# RTK_Mosaic_X5.net
KiCad netlist of a schematic drawn in EAGLE
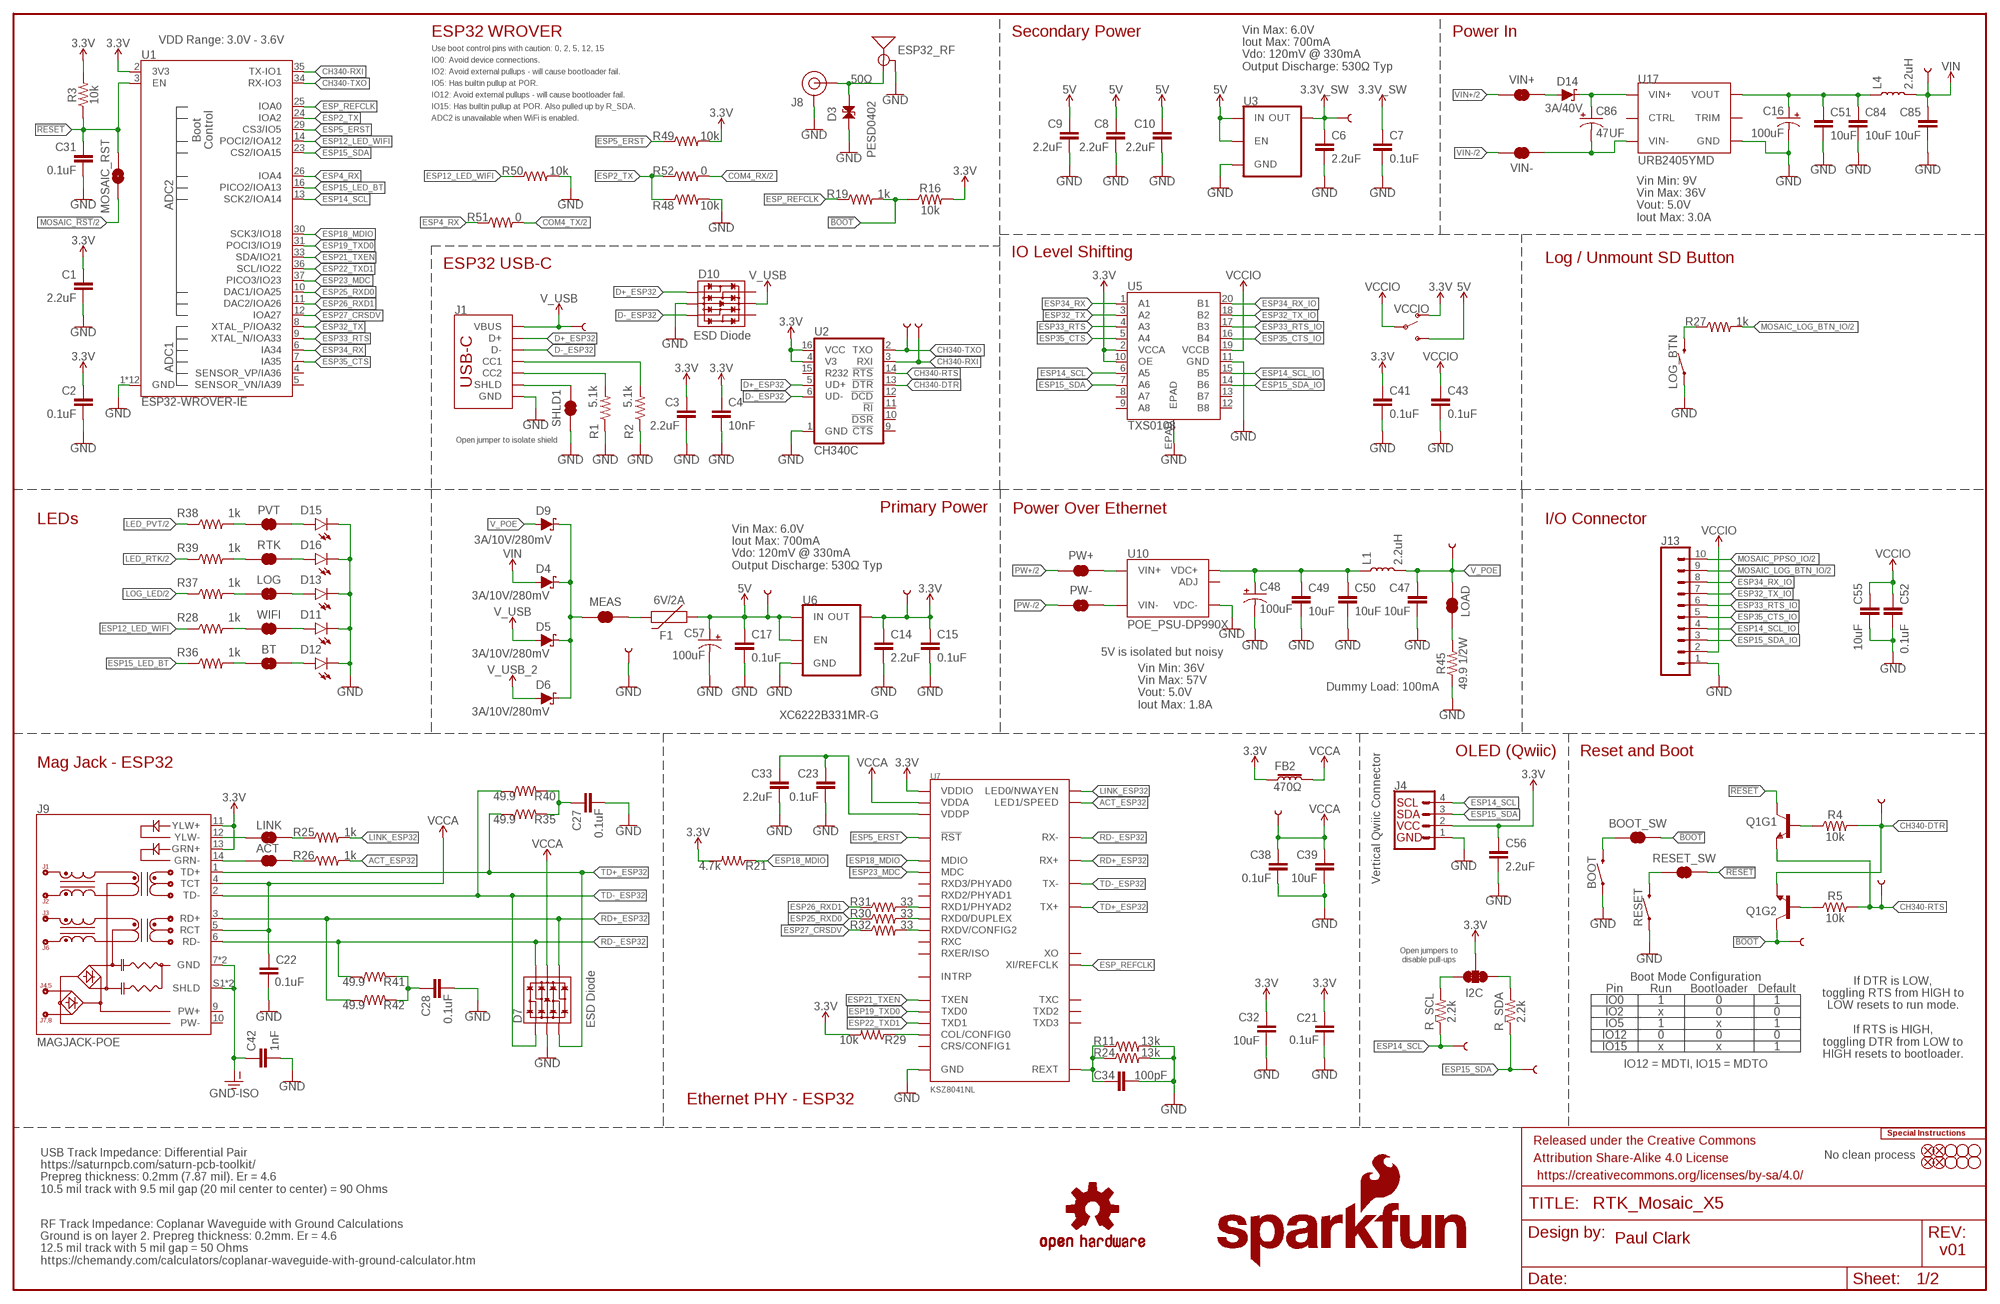
[diagram p0: schematic, sheet 1]
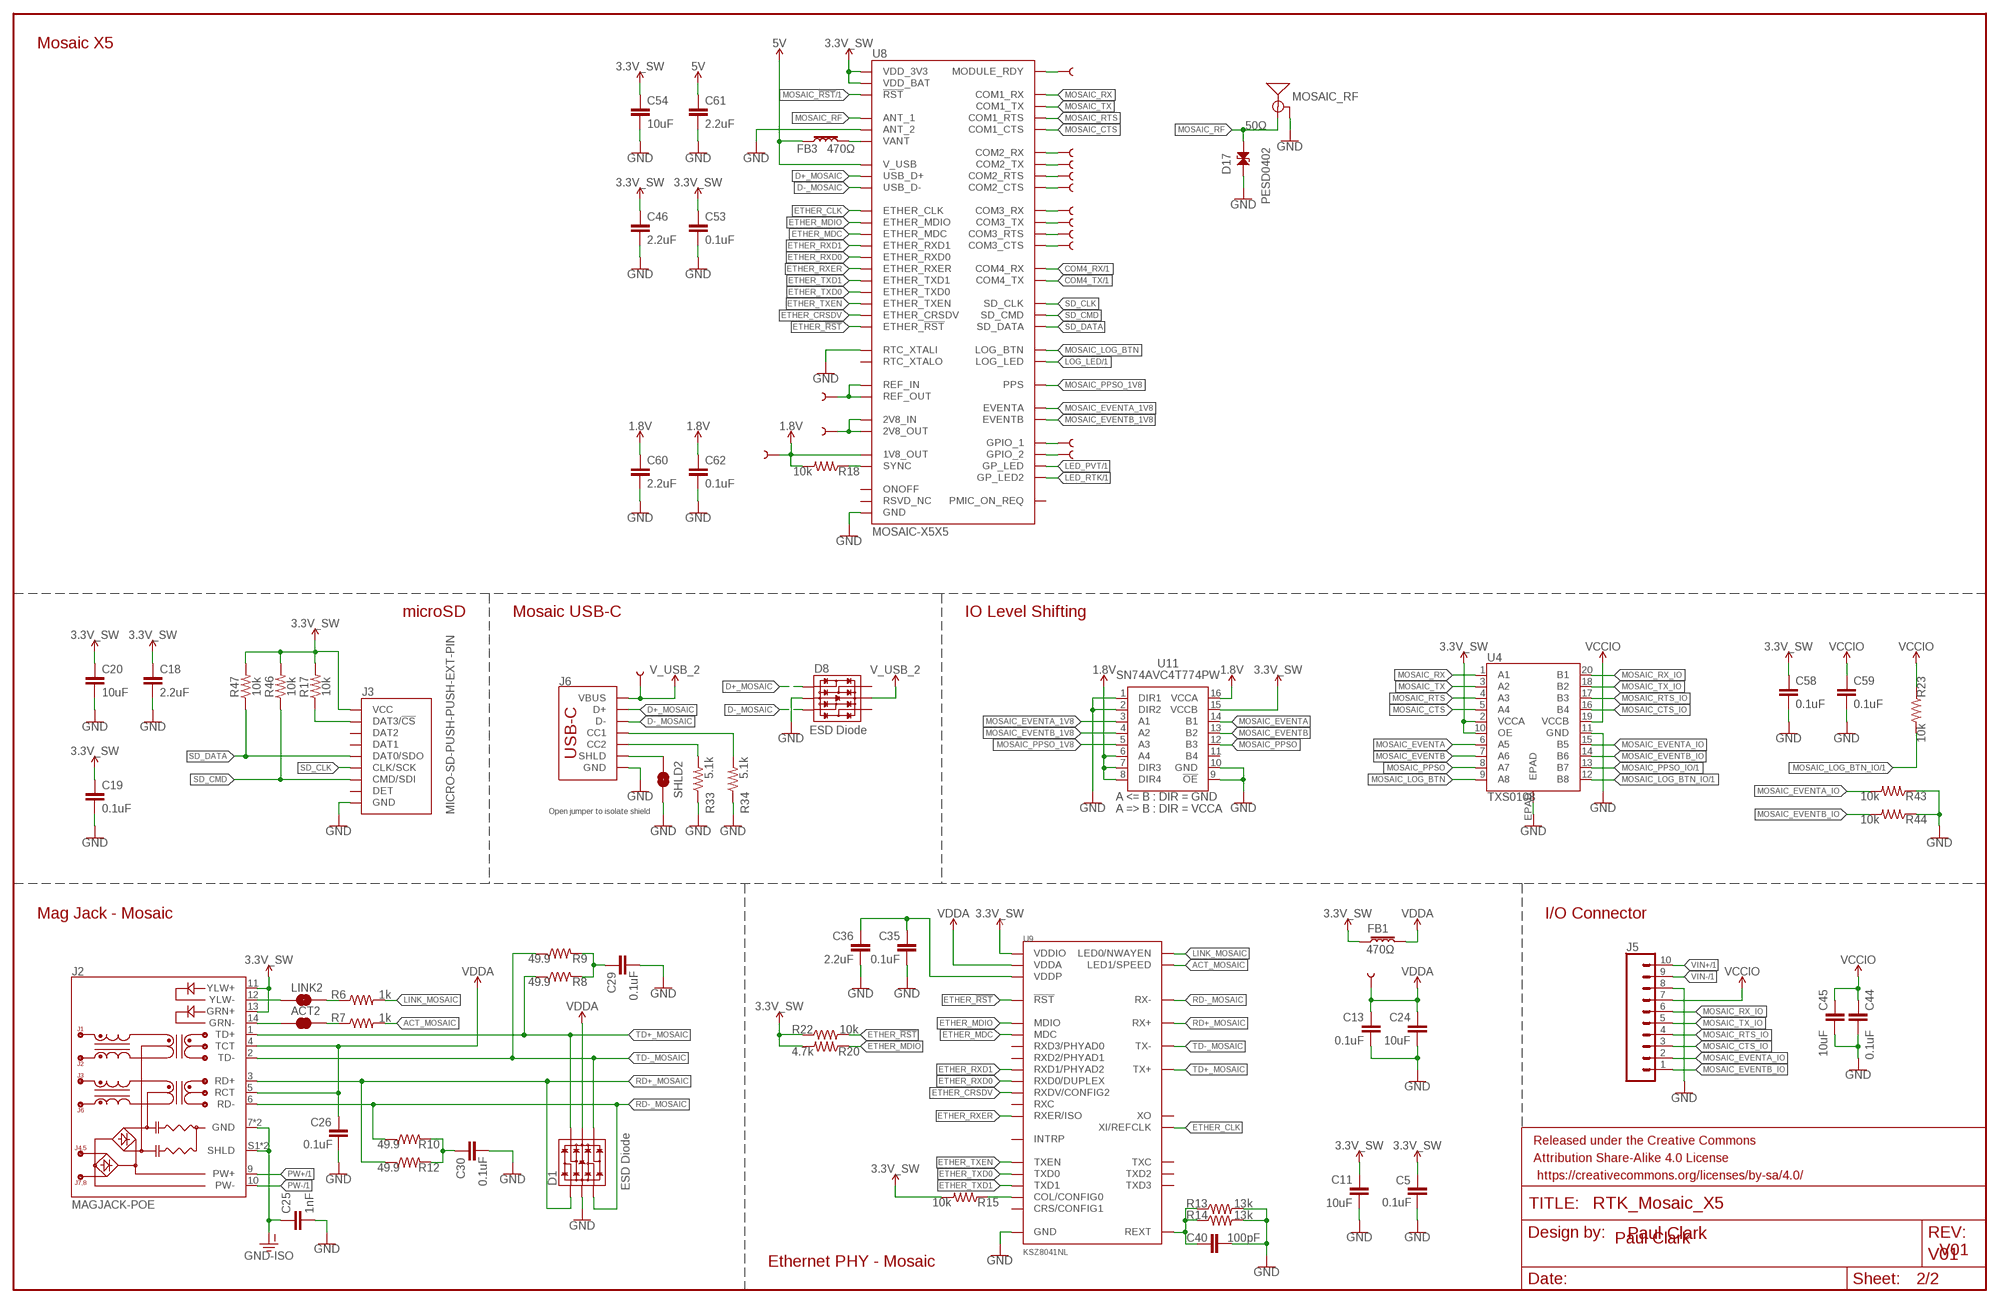
[diagram p1: schematic, sheet 2]

(export (version "E")
  (design (tool "Eeschema 10.0.6"))
  (components
    (comp (ref "3V3")
      (value "TEST-POINTPOGO_PTH")
      (footprint "eagle-import:1X01_NO_SILK")
      (libsource (lib "eagle-import") (part "TEST-POINTPOGO_PTH"))
    )
    (comp (ref "3V3_SW")
      (value "TEST-POINTPOGO_PTH")
      (footprint "eagle-import:1X01_NO_SILK")
      (libsource (lib "eagle-import") (part "TEST-POINTPOGO_PTH"))
    )
    (comp (ref "5V")
      (value "TEST-POINTPOGO_PTH")
      (footprint "eagle-import:1X01_NO_SILK")
      (libsource (lib "eagle-import") (part "TEST-POINTPOGO_PTH"))
    )
    (comp (ref "ACT")
      (value "JUMPER-SMT_2_NC_TRACE_SILK")
      (footprint "eagle-import:SMT-JUMPER_2_NC_TRACE_SILK")
      (libsource (lib "eagle-import") (part "JUMPER-SMT_2_NC_TRACE_SILK"))
    )
    (comp (ref "BOOT")
      (value "MOMENTARY-SWITCH-SPST-PTH-RIGHT-ANGLE-8-020")
      (footprint "eagle-import:TACTILE_SWITCH_PTH_RA_8-020")
      (libsource (lib "eagle-import") (part "MOMENTARY-SWITCH-SPST-PTH-RIGHT-ANGLE-8-020"))
    )
    (comp (ref "BOOT_SW")
      (value "JUMPER-SMT_2_NC_TRACE_SILK")
      (footprint "eagle-import:SMT-JUMPER_2_NC_TRACE_SILK")
      (libsource (lib "eagle-import") (part "JUMPER-SMT_2_NC_TRACE_SILK"))
    )
    (comp (ref "BT")
      (value "JUMPER-SMT_2_NC_TRACE_SILK")
      (footprint "eagle-import:SMT-JUMPER_2_NC_TRACE_SILK")
      (libsource (lib "eagle-import") (part "JUMPER-SMT_2_NC_TRACE_SILK"))
    )
    (comp (ref "C1")
      (value "2.2uF")
      (footprint "eagle-import:0603")
      (libsource (lib "eagle-import") (part "2.2UF-0603-10V-20%"))
    )
    (comp (ref "C2")
      (value "0.1uF")
      (footprint "eagle-import:0603")
      (libsource (lib "eagle-import") (part "0.1UF-0603-25V-5%"))
    )
    (comp (ref "C3")
      (value "2.2uF")
      (footprint "eagle-import:0603")
      (libsource (lib "eagle-import") (part "2.2UF-0603-10V-20%"))
    )
    (comp (ref "C4")
      (value "10nF")
      (footprint "eagle-import:0603")
      (libsource (lib "eagle-import") (part "10NF-0603-50V-10%"))
    )
    (comp (ref "C6")
      (value "2.2uF")
      (footprint "eagle-import:0603")
      (libsource (lib "eagle-import") (part "2.2UF-0603-10V-20%"))
    )
    (comp (ref "C7")
      (value "0.1uF")
      (footprint "eagle-import:0603")
      (libsource (lib "eagle-import") (part "0.1UF-0603-25V-5%"))
    )
    (comp (ref "C8")
      (value "2.2uF")
      (footprint "eagle-import:0603")
      (libsource (lib "eagle-import") (part "2.2UF-0603-10V-20%"))
    )
    (comp (ref "C9")
      (value "2.2uF")
      (footprint "eagle-import:0603")
      (libsource (lib "eagle-import") (part "2.2UF-0603-10V-20%"))
    )
    (comp (ref "C10")
      (value "2.2uF")
      (footprint "eagle-import:0603")
      (libsource (lib "eagle-import") (part "2.2UF-0603-10V-20%"))
    )
    (comp (ref "C14")
      (value "2.2uF")
      (footprint "eagle-import:0603")
      (libsource (lib "eagle-import") (part "2.2UF-0603-10V-20%"))
    )
    (comp (ref "C15")
      (value "0.1uF")
      (footprint "eagle-import:0603")
      (libsource (lib "eagle-import") (part "0.1UF-0603-25V-5%"))
    )
    (comp (ref "C16")
      (value "100uF")
      (footprint "eagle-import:PANASONIC_D")
      (libsource (lib "eagle-import") (part "100UF-POLAR-25V-20%(ELEC)"))
    )
    (comp (ref "C17")
      (value "0.1uF")
      (footprint "eagle-import:0603")
      (libsource (lib "eagle-import") (part "0.1UF-0603-25V-5%"))
    )
    (comp (ref "C21")
      (value "0.1uF")
      (footprint "eagle-import:0603")
      (libsource (lib "eagle-import") (part "0.1UF-0603-25V-5%"))
    )
    (comp (ref "C22")
      (value "0.1uF")
      (footprint "eagle-import:0603")
      (libsource (lib "eagle-import") (part "0.1UF-0603-25V-5%"))
    )
    (comp (ref "C23")
      (value "0.1uF")
      (footprint "eagle-import:0603")
      (libsource (lib "eagle-import") (part "0.1UF-0603-25V-5%"))
    )
    (comp (ref "C27")
      (value "0.1uF")
      (footprint "eagle-import:0603")
      (libsource (lib "eagle-import") (part "0.1UF-0603-25V-5%"))
    )
    (comp (ref "C28")
      (value "0.1uF")
      (footprint "eagle-import:0603")
      (libsource (lib "eagle-import") (part "0.1UF-0603-25V-5%"))
    )
    (comp (ref "C31")
      (value "0.1uF")
      (footprint "eagle-import:0603")
      (libsource (lib "eagle-import") (part "0.1UF-0603-25V-5%"))
    )
    (comp (ref "C32")
      (value "10uF")
      (footprint "eagle-import:0603")
      (libsource (lib "eagle-import") (part "10UF-0603-6.3V-20%"))
    )
    (comp (ref "C33")
      (value "2.2uF")
      (footprint "eagle-import:0603")
      (libsource (lib "eagle-import") (part "2.2UF-0603-10V-20%"))
    )
    (comp (ref "C34")
      (value "100pF")
      (footprint "eagle-import:0603")
      (libsource (lib "eagle-import") (part "100PF-0603-50V-5%"))
    )
    (comp (ref "C38")
      (value "0.1uF")
      (footprint "eagle-import:0603")
      (libsource (lib "eagle-import") (part "0.1UF-0603-25V-5%"))
    )
    (comp (ref "C39")
      (value "10uF")
      (footprint "eagle-import:0603")
      (libsource (lib "eagle-import") (part "10UF-0603-6.3V-20%"))
    )
    (comp (ref "C41")
      (value "0.1uF")
      (footprint "eagle-import:0603")
      (libsource (lib "eagle-import") (part "0.1UF-0603-25V-5%"))
    )
    (comp (ref "C42")
      (value "1nF")
      (footprint "eagle-import:1206")
      (libsource (lib "eagle-import") (part "1.0NF/1000PF-1206-2KV-10%"))
    )
    (comp (ref "C43")
      (value "0.1uF")
      (footprint "eagle-import:0603")
      (libsource (lib "eagle-import") (part "0.1UF-0603-25V-5%"))
    )
    (comp (ref "C47")
      (value "10uF")
      (footprint "eagle-import:0805")
      (libsource (lib "eagle-import") (part "10UF-0805-25V-10%"))
    )
    (comp (ref "C48")
      (value "100uF")
      (footprint "eagle-import:PANASONIC_D")
      (libsource (lib "eagle-import") (part "100UF-POLAR-25V-20%(ELEC)"))
    )
    (comp (ref "C49")
      (value "10uF")
      (footprint "eagle-import:0805")
      (libsource (lib "eagle-import") (part "10UF-0805-25V-10%"))
    )
    (comp (ref "C50")
      (value "10uF")
      (footprint "eagle-import:0805")
      (libsource (lib "eagle-import") (part "10UF-0805-25V-10%"))
    )
    (comp (ref "C51")
      (value "10uF")
      (footprint "eagle-import:0805")
      (libsource (lib "eagle-import") (part "10UF-0805-25V-10%"))
    )
    (comp (ref "C52")
      (value "0.1uF")
      (footprint "eagle-import:0603")
      (libsource (lib "eagle-import") (part "0.1UF-0603-25V-5%"))
    )
    (comp (ref "C55")
      (value "10uF")
      (footprint "eagle-import:0603")
      (libsource (lib "eagle-import") (part "10UF-0603-6.3V-20%"))
    )
    (comp (ref "C56")
      (value "2.2uF")
      (footprint "eagle-import:0603")
      (libsource (lib "eagle-import") (part "2.2UF-0603-10V-20%"))
    )
    (comp (ref "C57")
      (value "100uF")
      (footprint "eagle-import:PANASONIC_D")
      (libsource (lib "eagle-import") (part "100UF-POLAR-25V-20%(ELEC)"))
    )
    (comp (ref "C84")
      (value "10uF")
      (footprint "eagle-import:0805")
      (libsource (lib "eagle-import") (part "10UF-0805-25V-10%"))
    )
    (comp (ref "C85")
      (value "10uF")
      (footprint "eagle-import:0805")
      (libsource (lib "eagle-import") (part "10UF-0805-25V-10%"))
    )
    (comp (ref "C86")
      (value "47UF")
      (footprint "eagle-import:PANASONIC_D")
      (libsource (lib "eagle-import") (part "47UF-POLAR-PANASONIC_D-50V-20%"))
    )
    (comp (ref "D3")
      (value "PESD0402")
      (footprint "eagle-import:0402")
      (fields
        (field (name "DIGIKEY_PART") "PESD0402-140CT-ND")
        (field (name "MOUSE_PART") "650-PESD0402-140")
      )
      (libsource (lib "eagle-import") (part "PESD0402-0402"))
    )
    (comp (ref "D4")
      (value "3A/10V/280mV")
      (footprint "eagle-import:SOD-323")
      (libsource (lib "eagle-import") (part "DIODE-SCHOTTKY-BAT60A"))
    )
    (comp (ref "D5")
      (value "3A/10V/280mV")
      (footprint "eagle-import:SOD-323")
      (libsource (lib "eagle-import") (part "DIODE-SCHOTTKY-BAT60A"))
    )
    (comp (ref "D6")
      (value "3A/10V/280mV")
      (footprint "eagle-import:SOD-323")
      (libsource (lib "eagle-import") (part "DIODE-SCHOTTKY-BAT60A"))
    )
    (comp (ref "D7")
      (value "ESD Diode")
      (footprint "eagle-import:SOT-23-6")
      (libsource (lib "eagle-import") (part "TVS_DIODE_ARRAY_DT1042-04SO-7"))
    )
    (comp (ref "D9")
      (value "3A/10V/280mV")
      (footprint "eagle-import:SOD-323")
      (libsource (lib "eagle-import") (part "DIODE-SCHOTTKY-BAT60A"))
    )
    (comp (ref "D10")
      (value "ESD Diode")
      (footprint "eagle-import:SOT-23-6")
      (libsource (lib "eagle-import") (part "TVS_DIODE_ARRAY_DT1042-04SO-7"))
    )
    (comp (ref "D11")
      (value "LED-RIGHT-ANGLE-PTH-AMBER")
      (footprint "eagle-import:CBI-RIGHT-ANGLE-PTH")
      (libsource (lib "eagle-import") (part "LED-RIGHT-ANGLE-PTH-AMBER"))
    )
    (comp (ref "D12")
      (value "LED-RIGHT-ANGLE-PTH-BLUE")
      (footprint "eagle-import:CBI-RIGHT-ANGLE-PTH")
      (libsource (lib "eagle-import") (part "LED-RIGHT-ANGLE-PTH-BLUE"))
    )
    (comp (ref "D13")
      (value "LED-RIGHT-ANGLE-PTH-GREEN")
      (footprint "eagle-import:CBI-RIGHT-ANGLE-PTH")
      (libsource (lib "eagle-import") (part "LED-RIGHT-ANGLE-PTH-GREEN"))
    )
    (comp (ref "D14")
      (value "3A/40V")
      (footprint "eagle-import:SMA-DIODE")
      (libsource (lib "eagle-import") (part "DIODE-SCHOTTKY-B340A"))
    )
    (comp (ref "D15")
      (value "LED-RIGHT-ANGLE-PTH-BLUE")
      (footprint "eagle-import:CBI-RIGHT-ANGLE-PTH")
      (libsource (lib "eagle-import") (part "LED-RIGHT-ANGLE-PTH-BLUE"))
    )
    (comp (ref "D16")
      (value "LED-RIGHT-ANGLE-PTH-BLUE")
      (footprint "eagle-import:CBI-RIGHT-ANGLE-PTH")
      (libsource (lib "eagle-import") (part "LED-RIGHT-ANGLE-PTH-BLUE"))
    )
    (comp (ref "DTR")
      (value "TEST-POINTPOGO_PTH")
      (footprint "eagle-import:1X01_NO_SILK")
      (libsource (lib "eagle-import") (part "TEST-POINTPOGO_PTH"))
    )
    (comp (ref "ESP32_RF")
      (value "ANTENNA-SMA-GROUNDEDEDGE_RPSMA")
      (footprint "eagle-import:RP-SMA-EDGE")
      (libsource (lib "eagle-import") (part "ANTENNA-SMA-GROUNDEDEDGE_RPSMA"))
    )
    (comp (ref "F1")
      (value "6V/2A")
      (footprint "eagle-import:1210")
      (libsource (lib "eagle-import") (part "PPTC_6V2A"))
    )
    (comp (ref "FB2")
      (value "470Ω")
      (footprint "eagle-import:0603")
      (libsource (lib "eagle-import") (part "FERRITE_BEAD-0603-470Ω-100MHZ-1A-200MILIΩ"))
    )
    (comp (ref "FD1")
      (value "FIDUCIAL1X2")
      (footprint "eagle-import:FIDUCIAL-1X2")
      (libsource (lib "eagle-import") (part "FIDUCIAL1X2"))
    )
    (comp (ref "FD2")
      (value "FIDUCIAL1X2")
      (footprint "eagle-import:FIDUCIAL-1X2")
      (libsource (lib "eagle-import") (part "FIDUCIAL1X2"))
    )
    (comp (ref "FD3")
      (value "FIDUCIAL1X2")
      (footprint "eagle-import:FIDUCIAL-1X2")
      (libsource (lib "eagle-import") (part "FIDUCIAL1X2"))
    )
    (comp (ref "FD4")
      (value "FIDUCIAL1X2")
      (footprint "eagle-import:FIDUCIAL-1X2")
      (libsource (lib "eagle-import") (part "FIDUCIAL1X2"))
    )
    (comp (ref "FRAME1")
      (value "FRAME-LEDGER")
      (footprint "eagle-import:CREATIVE_COMMONS")
      (libsource (lib "eagle-import") (part "FRAME-LEDGER"))
    )
    (comp (ref "GND")
      (value "TEST-POINTPOGO_PTH")
      (footprint "eagle-import:1X01_NO_SILK")
      (libsource (lib "eagle-import") (part "TEST-POINTPOGO_PTH"))
    )
    (comp (ref "H1")
      (value "STAND-OFFTIGHT")
      (footprint "eagle-import:STAND-OFF-TIGHT")
      (libsource (lib "eagle-import") (part "STAND-OFFTIGHT"))
    )
    (comp (ref "H2")
      (value "STAND-OFFTIGHT")
      (footprint "eagle-import:STAND-OFF-TIGHT")
      (libsource (lib "eagle-import") (part "STAND-OFFTIGHT"))
    )
    (comp (ref "H3")
      (value "STAND-OFFTIGHT")
      (footprint "eagle-import:STAND-OFF-TIGHT")
      (libsource (lib "eagle-import") (part "STAND-OFFTIGHT"))
    )
    (comp (ref "H4")
      (value "STAND-OFFTIGHT")
      (footprint "eagle-import:STAND-OFF-TIGHT")
      (libsource (lib "eagle-import") (part "STAND-OFFTIGHT"))
    )
    (comp (ref "H5")
      (value "STAND-OFFTIGHT")
      (footprint "eagle-import:STAND-OFF-TIGHT")
      (libsource (lib "eagle-import") (part "STAND-OFFTIGHT"))
    )
    (comp (ref "H6")
      (value "STAND-OFFTIGHT")
      (footprint "eagle-import:STAND-OFF-TIGHT")
      (libsource (lib "eagle-import") (part "STAND-OFFTIGHT"))
    )
    (comp (ref "I2C")
      (value "JUMPER-SMT_3_2-NC_TRACE_SILK")
      (footprint "eagle-import:SMT-JUMPER_3_2-NC_TRACE_SILK")
      (libsource (lib "eagle-import") (part "JUMPER-SMT_3_2-NC_TRACE_SILK"))
    )
    (comp (ref "J1")
      (value "USB_C_4-LAYER_PADS")
      (footprint "eagle-import:USB-C-16P_4LAYER-PADS")
      (libsource (lib "eagle-import") (part "USB_C_4-LAYER_PADS"))
    )
    (comp (ref "J4")
      (value "Vertical Qwiic Connector")
      (footprint "eagle-import:JST04_1MM_VERT")
      (libsource (lib "eagle-import") (part "QWIIC_CONNECTOR"))
    )
    (comp (ref "J8")
      (value "U.FL2PIN-REDUCED-FOOTPRINT")
      (footprint "eagle-import:U.FL_REDUCED_FOOTPRINT")
      (libsource (lib "eagle-import") (part "U.FL2PIN-REDUCED-FOOTPRINT"))
    )
    (comp (ref "J9")
      (value "MAGJACK-POE")
      (footprint "eagle-import:MAGJACK-SYM_LED")
      (libsource (lib "eagle-import") (part "MAGJACK-POE"))
    )
    (comp (ref "J13")
      (value "CONN_10_3.5MM_RA_HEADER")
      (footprint "eagle-import:1X10_SCREW_TERMINAL_3.5MM")
      (libsource (lib "eagle-import") (part "CONN_10_3.5MM_RA_HEADER"))
    )
    (comp (ref "L1")
      (value "2.2uH")
      (footprint "eagle-import:0805-WIDE")
      (libsource (lib "eagle-import") (part "INDUCTOR-0805_WIDE-2.2UH"))
    )
    (comp (ref "L4")
      (value "2.2uH")
      (footprint "eagle-import:0805-WIDE")
      (libsource (lib "eagle-import") (part "INDUCTOR-0805_WIDE-2.2UH"))
    )
    (comp (ref "LINK")
      (value "JUMPER-SMT_2_NC_TRACE_SILK")
      (footprint "eagle-import:SMT-JUMPER_2_NC_TRACE_SILK")
      (libsource (lib "eagle-import") (part "JUMPER-SMT_2_NC_TRACE_SILK"))
    )
    (comp (ref "LOAD")
      (value "JUMPER-SMT_2_NC_TRACE_SILK")
      (footprint "eagle-import:SMT-JUMPER_2_NC_TRACE_SILK")
      (libsource (lib "eagle-import") (part "JUMPER-SMT_2_NC_TRACE_SILK"))
    )
    (comp (ref "LOG")
      (value "JUMPER-SMT_2_NC_TRACE_SILK")
      (footprint "eagle-import:SMT-JUMPER_2_NC_TRACE_SILK")
      (libsource (lib "eagle-import") (part "JUMPER-SMT_2_NC_TRACE_SILK"))
    )
    (comp (ref "LOGO1")
      (value "SPECIAL_INSTRUCTIONS-ORDERING")
      (footprint "eagle-import:ORDERING_INSTRUCTIONS")
      (libsource (lib "eagle-import") (part "SPECIAL_INSTRUCTIONS-ORDERING"))
    )
    (comp (ref "LOGO4")
      (value "OSHW-LOGOS")
      (footprint "eagle-import:OSHW-LOGO-S")
      (libsource (lib "eagle-import") (part "OSHW-LOGOS"))
    )
    (comp (ref "LOGO5")
      (value "SFE_LOGO_NAME.2_INCH")
      (footprint "eagle-import:SFE_LOGO_NAME_.2")
      (libsource (lib "eagle-import") (part "SFE_LOGO_NAME.2_INCH"))
    )
    (comp (ref "LOGO6")
      (value "SFE_LOGO_FLAME.2_INCH")
      (footprint "eagle-import:SFE_LOGO_FLAME_.2")
      (libsource (lib "eagle-import") (part "SFE_LOGO_FLAME.2_INCH"))
    )
    (comp (ref "LOG_BTN")
      (value "MOMENTARY-SWITCH-SPST-PTH-RIGHT-ANGLE-8-020")
      (footprint "eagle-import:TACTILE_SWITCH_PTH_RA_8-020")
      (libsource (lib "eagle-import") (part "MOMENTARY-SWITCH-SPST-PTH-RIGHT-ANGLE-8-020"))
    )
    (comp (ref "MEAS")
      (value "JUMPER-COMBO_2_NC_TRACE")
      (footprint "eagle-import:COMBO-JUMPER_2_NC_TRACE")
      (libsource (lib "eagle-import") (part "JUMPER-COMBO_2_NC_TRACE"))
    )
    (comp (ref "MOSAIC_RST")
      (value "JUMPER-COMBO_2_NO")
      (footprint "eagle-import:COMBO-JUMPER_2_NO")
      (libsource (lib "eagle-import") (part "JUMPER-COMBO_2_NO"))
    )
    (comp (ref "PVT")
      (value "JUMPER-SMT_2_NC_TRACE_SILK")
      (footprint "eagle-import:SMT-JUMPER_2_NC_TRACE_SILK")
      (libsource (lib "eagle-import") (part "JUMPER-SMT_2_NC_TRACE_SILK"))
    )
    (comp (ref "PW+")
      (value "JUMPER-COMBO_2_NC_TRACE")
      (footprint "eagle-import:COMBO-JUMPER_2_NC_TRACE")
      (libsource (lib "eagle-import") (part "JUMPER-COMBO_2_NC_TRACE"))
    )
    (comp (ref "PW-")
      (value "JUMPER-COMBO_2_NC_TRACE")
      (footprint "eagle-import:COMBO-JUMPER_2_NC_TRACE")
      (libsource (lib "eagle-import") (part "JUMPER-COMBO_2_NC_TRACE"))
    )
    (comp (ref "Q1")
      (value "TRANS_NPN_DUAL-MBT3904DW1T1")
      (footprint "eagle-import:SC70-6")
      (libsource (lib "eagle-import") (part "TRANS_NPN_DUAL-MBT3904DW1T1"))
    )
    (comp (ref "R1")
      (value "5.1k")
      (footprint "eagle-import:0603")
      (libsource (lib "eagle-import") (part "5.1KOHM5.1KOHM-0603-1/10W-1%"))
    )
    (comp (ref "R2")
      (value "5.1k")
      (footprint "eagle-import:0603")
      (libsource (lib "eagle-import") (part "5.1KOHM5.1KOHM-0603-1/10W-1%"))
    )
    (comp (ref "R3")
      (value "10k")
      (footprint "eagle-import:0603")
      (libsource (lib "eagle-import") (part "10KOHM-0603-1/10W-1%"))
    )
    (comp (ref "R4")
      (value "10k")
      (footprint "eagle-import:0603")
      (libsource (lib "eagle-import") (part "10KOHM-0603-1/10W-1%"))
    )
    (comp (ref "R5")
      (value "10k")
      (footprint "eagle-import:0603")
      (libsource (lib "eagle-import") (part "10KOHM-0603-1/10W-1%"))
    )
    (comp (ref "R11")
      (value "13k")
      (footprint "eagle-import:0603")
      (libsource (lib "eagle-import") (part "13KOHM-0603-1/10W-1%"))
    )
    (comp (ref "R16")
      (value "10k")
      (footprint "eagle-import:0603")
      (libsource (lib "eagle-import") (part "10KOHM-0603-1/10W-1%"))
    )
    (comp (ref "R19")
      (value "1k")
      (footprint "eagle-import:0603")
      (libsource (lib "eagle-import") (part "1KOHM-0603-1/10W-1%"))
    )
    (comp (ref "R21")
      (value "4.7k")
      (footprint "eagle-import:0603")
      (libsource (lib "eagle-import") (part "4.7KOHM-0603-1/10W-1%"))
    )
    (comp (ref "R24")
      (value "13k")
      (footprint "eagle-import:0603")
      (libsource (lib "eagle-import") (part "13KOHM-0603-1/10W-1%"))
    )
    (comp (ref "R25")
      (value "1k")
      (footprint "eagle-import:0603")
      (libsource (lib "eagle-import") (part "1KOHM-0603-1/10W-1%"))
    )
    (comp (ref "R26")
      (value "1k")
      (footprint "eagle-import:0603")
      (libsource (lib "eagle-import") (part "1KOHM-0603-1/10W-1%"))
    )
    (comp (ref "R27")
      (value "1k")
      (footprint "eagle-import:0603")
      (libsource (lib "eagle-import") (part "1KOHM-0603-1/10W-1%"))
    )
    (comp (ref "R28")
      (value "1k")
      (footprint "eagle-import:0603")
      (libsource (lib "eagle-import") (part "1KOHM-0603-1/10W-1%"))
    )
    (comp (ref "R29")
      (value "10k")
      (footprint "eagle-import:0603")
      (libsource (lib "eagle-import") (part "10KOHM-0603-1/10W-1%"))
    )
    (comp (ref "R30")
      (value "33")
      (footprint "eagle-import:0603")
      (libsource (lib "eagle-import") (part "33OHM-0603-1/10W-1%"))
    )
    (comp (ref "R31")
      (value "33")
      (footprint "eagle-import:0603")
      (libsource (lib "eagle-import") (part "33OHM-0603-1/10W-1%"))
    )
    (comp (ref "R32")
      (value "33")
      (footprint "eagle-import:0603")
      (libsource (lib "eagle-import") (part "33OHM-0603-1/10W-1%"))
    )
    (comp (ref "R35")
      (value "49.9")
      (footprint "eagle-import:0603")
      (libsource (lib "eagle-import") (part "49.9OHM-0603-1/10W-1%"))
    )
    (comp (ref "R36")
      (value "1k")
      (footprint "eagle-import:0603")
      (libsource (lib "eagle-import") (part "1KOHM-0603-1/10W-1%"))
    )
    (comp (ref "R37")
      (value "1k")
      (footprint "eagle-import:0603")
      (libsource (lib "eagle-import") (part "1KOHM-0603-1/10W-1%"))
    )
    (comp (ref "R38")
      (value "1k")
      (footprint "eagle-import:0603")
      (libsource (lib "eagle-import") (part "1KOHM-0603-1/10W-1%"))
    )
    (comp (ref "R39")
      (value "1k")
      (footprint "eagle-import:0603")
      (libsource (lib "eagle-import") (part "1KOHM-0603-1/10W-1%"))
    )
    (comp (ref "R40")
      (value "49.9")
      (footprint "eagle-import:0603")
      (libsource (lib "eagle-import") (part "49.9OHM-0603-1/10W-1%"))
    )
    (comp (ref "R41")
      (value "49.9")
      (footprint "eagle-import:0603")
      (libsource (lib "eagle-import") (part "49.9OHM-0603-1/10W-1%"))
    )
    (comp (ref "R42")
      (value "49.9")
      (footprint "eagle-import:0603")
      (libsource (lib "eagle-import") (part "49.9OHM-0603-1/10W-1%"))
    )
    (comp (ref "R45")
      (value "49.9 1/2W")
      (footprint "eagle-import:1206")
      (libsource (lib "eagle-import") (part "49.9OHM-1206-1/2W-1%"))
    )
    (comp (ref "R48")
      (value "10k")
      (footprint "eagle-import:0603")
      (libsource (lib "eagle-import") (part "10KOHM-0603-1/10W-1%"))
    )
    (comp (ref "R49")
      (value "10k")
      (footprint "eagle-import:0603")
      (libsource (lib "eagle-import") (part "10KOHM-0603-1/10W-1%"))
    )
    (comp (ref "R50")
      (value "10k")
      (footprint "eagle-import:0603")
      (libsource (lib "eagle-import") (part "10KOHM-0603-1/10W-1%"))
    )
    (comp (ref "R51")
      (value "0")
      (footprint "eagle-import:0603")
      (libsource (lib "eagle-import") (part "0OHM-0603-1/10W"))
    )
    (comp (ref "R52")
      (value "0")
      (footprint "eagle-import:0603")
      (libsource (lib "eagle-import") (part "0OHM-0603-1/10W"))
    )
    (comp (ref "RESET")
      (value "MOMENTARY-SWITCH-SPST-PTH-RIGHT-ANGLE-8-020")
      (footprint "eagle-import:TACTILE_SWITCH_PTH_RA_8-020")
      (libsource (lib "eagle-import") (part "MOMENTARY-SWITCH-SPST-PTH-RIGHT-ANGLE-8-020"))
    )
    (comp (ref "RESET_SW")
      (value "JUMPER-SMT_2_NC_TRACE_SILK")
      (footprint "eagle-import:SMT-JUMPER_2_NC_TRACE_SILK")
      (libsource (lib "eagle-import") (part "JUMPER-SMT_2_NC_TRACE_SILK"))
    )
    (comp (ref "RTK")
      (value "JUMPER-SMT_2_NC_TRACE_SILK")
      (footprint "eagle-import:SMT-JUMPER_2_NC_TRACE_SILK")
      (libsource (lib "eagle-import") (part "JUMPER-SMT_2_NC_TRACE_SILK"))
    )
    (comp (ref "RTS")
      (value "TEST-POINTPOGO_PTH")
      (footprint "eagle-import:1X01_NO_SILK")
      (libsource (lib "eagle-import") (part "TEST-POINTPOGO_PTH"))
    )
    (comp (ref "RX")
      (value "TEST-POINTPOGO_PTH")
      (footprint "eagle-import:1X01_NO_SILK")
      (libsource (lib "eagle-import") (part "TEST-POINTPOGO_PTH"))
    )
    (comp (ref "R_SCL")
      (value "2.2k")
      (footprint "eagle-import:0603")
      (libsource (lib "eagle-import") (part "2.2KOHM-0603-1/10W-1%"))
    )
    (comp (ref "R_SDA")
      (value "2.2k")
      (footprint "eagle-import:0603")
      (libsource (lib "eagle-import") (part "2.2KOHM-0603-1/10W-1%"))
    )
    (comp (ref "SCL2")
      (value "TEST-POINTPOGO_PTH")
      (footprint "eagle-import:1X01_NO_SILK")
      (libsource (lib "eagle-import") (part "TEST-POINTPOGO_PTH"))
    )
    (comp (ref "SDA2")
      (value "TEST-POINTPOGO_PTH")
      (footprint "eagle-import:1X01_NO_SILK")
      (libsource (lib "eagle-import") (part "TEST-POINTPOGO_PTH"))
    )
    (comp (ref "SHLD1")
      (value "JUMPER-SMT_2_NC_TRACE_SILK")
      (footprint "eagle-import:SMT-JUMPER_2_NC_TRACE_SILK")
      (libsource (lib "eagle-import") (part "JUMPER-SMT_2_NC_TRACE_SILK"))
    )
    (comp (ref "TP_BOOT")
      (value "TEST-POINTPOGO_PTH")
      (footprint "eagle-import:1X01_NO_SILK")
      (libsource (lib "eagle-import") (part "TEST-POINTPOGO_PTH"))
    )
    (comp (ref "TX")
      (value "TEST-POINTPOGO_PTH")
      (footprint "eagle-import:1X01_NO_SILK")
      (libsource (lib "eagle-import") (part "TEST-POINTPOGO_PTH"))
    )
    (comp (ref "U1")
      (value "ESP32-WROVER-IE")
      (footprint "eagle-import:ESP32-WROVER-E_IE")
      (libsource (lib "eagle-import") (part "ESP32-WROVER-E/IE_IE-N16R8"))
    )
    (comp (ref "U2")
      (value "CH340C")
      (footprint "eagle-import:SO016")
      (libsource (lib "eagle-import") (part "CH340C"))
    )
    (comp (ref "U3")
      (value "XC6222B331MR-G")
      (footprint "eagle-import:SOT23-5")
      (libsource (lib "eagle-import") (part "XC6222B331MR-G"))
    )
    (comp (ref "U5")
      (value "TXS0108")
      (footprint "eagle-import:VFQFN-20")
      (libsource (lib "eagle-import") (part "TXS0108-VFQFN_20"))
    )
    (comp (ref "U6")
      (value "XC6222B331MR-G")
      (footprint "eagle-import:SOT23-5")
      (libsource (lib "eagle-import") (part "XC6222B331MR-G"))
    )
    (comp (ref "U7")
      (value "KSZ8041NL")
      (footprint "eagle-import:MLF55Q-32LD")
      (libsource (lib "eagle-import") (part "KSZ8041NL"))
    )
    (comp (ref "U10")
      (value "POE_PSU-DP990X")
      (footprint "eagle-import:DP990X")
      (libsource (lib "eagle-import") (part "POE_PSU-DP990X"))
    )
    (comp (ref "U17")
      (value "URB2405YMD")
      (footprint "eagle-import:URB_YMD-15WR3")
      (libsource (lib "eagle-import") (part "URB_YMD-15WR3__URB2405YMD-15WR3"))
    )
    (comp (ref "VCCA")
      (value "TEST-POINTPOGO_PTH")
      (footprint "eagle-import:1X01_NO_SILK")
      (libsource (lib "eagle-import") (part "TEST-POINTPOGO_PTH"))
    )
    (comp (ref "VCCIO")
      (value "SWITCH-SPDT-SMD-AYZ0202")
      (footprint "eagle-import:SWITCH_DPDT_SMD_AYZ0202")
      (libsource (lib "eagle-import") (part "SWITCH-SPDT-SMD-AYZ0202"))
    )
    (comp (ref "VIN")
      (value "TEST-POINTPOGO_PTH")
      (footprint "eagle-import:1X01_NO_SILK")
      (libsource (lib "eagle-import") (part "TEST-POINTPOGO_PTH"))
    )
    (comp (ref "VIN+")
      (value "JUMPER-COMBO_2_NC_TRACE")
      (footprint "eagle-import:COMBO-JUMPER_2_NC_TRACE")
      (libsource (lib "eagle-import") (part "JUMPER-COMBO_2_NC_TRACE"))
    )
    (comp (ref "VIN-")
      (value "JUMPER-COMBO_2_NC_TRACE")
      (footprint "eagle-import:COMBO-JUMPER_2_NC_TRACE")
      (libsource (lib "eagle-import") (part "JUMPER-COMBO_2_NC_TRACE"))
    )
    (comp (ref "VPOE")
      (value "TEST-POINTPOGO_PTH")
      (footprint "eagle-import:1X01_NO_SILK")
      (libsource (lib "eagle-import") (part "TEST-POINTPOGO_PTH"))
    )
    (comp (ref "VUSB")
      (value "TEST-POINTPOGO_PTH")
      (footprint "eagle-import:1X01_NO_SILK")
      (libsource (lib "eagle-import") (part "TEST-POINTPOGO_PTH"))
    )
    (comp (ref "WIFI")
      (value "JUMPER-SMT_2_NC_TRACE_SILK")
      (footprint "eagle-import:SMT-JUMPER_2_NC_TRACE_SILK")
      (libsource (lib "eagle-import") (part "JUMPER-SMT_2_NC_TRACE_SILK"))
    )
    (comp (ref "1V8")
      (value "TEST-POINTPOGO_PTH")
      (footprint "eagle-import:1X01_NO_SILK")
      (libsource (lib "eagle-import") (part "TEST-POINTPOGO_PTH"))
    )
    (comp (ref "2V8")
      (value "TEST-POINTPOGO_PTH")
      (footprint "eagle-import:1X01_NO_SILK")
      (libsource (lib "eagle-import") (part "TEST-POINTPOGO_PTH"))
    )
    (comp (ref "ACT2")
      (value "JUMPER-SMT_2_NC_TRACE_SILK")
      (footprint "eagle-import:SMT-JUMPER_2_NC_TRACE_SILK")
      (libsource (lib "eagle-import") (part "JUMPER-SMT_2_NC_TRACE_SILK"))
    )
    (comp (ref "C5")
      (value "0.1uF")
      (footprint "eagle-import:0603")
      (libsource (lib "eagle-import") (part "0.1UF-0603-25V-5%"))
    )
    (comp (ref "C11")
      (value "10uF")
      (footprint "eagle-import:0603")
      (libsource (lib "eagle-import") (part "10UF-0603-6.3V-20%"))
    )
    (comp (ref "C13")
      (value "0.1uF")
      (footprint "eagle-import:0603")
      (libsource (lib "eagle-import") (part "0.1UF-0603-25V-5%"))
    )
    (comp (ref "C18")
      (value "2.2uF")
      (footprint "eagle-import:0603")
      (libsource (lib "eagle-import") (part "2.2UF-0603-10V-20%"))
    )
    (comp (ref "C19")
      (value "0.1uF")
      (footprint "eagle-import:0603")
      (libsource (lib "eagle-import") (part "0.1UF-0603-25V-5%"))
    )
    (comp (ref "C20")
      (value "10uF")
      (footprint "eagle-import:0603")
      (libsource (lib "eagle-import") (part "10UF-0603-6.3V-20%"))
    )
    (comp (ref "C24")
      (value "10uF")
      (footprint "eagle-import:0603")
      (libsource (lib "eagle-import") (part "10UF-0603-6.3V-20%"))
    )
    (comp (ref "C25")
      (value "1nF")
      (footprint "eagle-import:1206")
      (libsource (lib "eagle-import") (part "1.0NF/1000PF-1206-2KV-10%"))
    )
    (comp (ref "C26")
      (value "0.1uF")
      (footprint "eagle-import:0603")
      (libsource (lib "eagle-import") (part "0.1UF-0603-25V-5%"))
    )
    (comp (ref "C29")
      (value "0.1uF")
      (footprint "eagle-import:0603")
      (libsource (lib "eagle-import") (part "0.1UF-0603-25V-5%"))
    )
    (comp (ref "C30")
      (value "0.1uF")
      (footprint "eagle-import:0603")
      (libsource (lib "eagle-import") (part "0.1UF-0603-25V-5%"))
    )
    (comp (ref "C35")
      (value "0.1uF")
      (footprint "eagle-import:0603")
      (libsource (lib "eagle-import") (part "0.1UF-0603-25V-5%"))
    )
    (comp (ref "C36")
      (value "2.2uF")
      (footprint "eagle-import:0603")
      (libsource (lib "eagle-import") (part "2.2UF-0603-10V-20%"))
    )
    (comp (ref "C40")
      (value "100pF")
      (footprint "eagle-import:0603")
      (libsource (lib "eagle-import") (part "100PF-0603-50V-5%"))
    )
    (comp (ref "C44")
      (value "0.1uF")
      (footprint "eagle-import:0603")
      (libsource (lib "eagle-import") (part "0.1UF-0603-25V-5%"))
    )
    (comp (ref "C45")
      (value "10uF")
      (footprint "eagle-import:0603")
      (libsource (lib "eagle-import") (part "10UF-0603-6.3V-20%"))
    )
    (comp (ref "C46")
      (value "2.2uF")
      (footprint "eagle-import:0603")
      (libsource (lib "eagle-import") (part "2.2UF-0603-10V-20%"))
    )
    (comp (ref "C53")
      (value "0.1uF")
      (footprint "eagle-import:0603")
      (libsource (lib "eagle-import") (part "0.1UF-0603-25V-5%"))
    )
    (comp (ref "C54")
      (value "10uF")
      (footprint "eagle-import:0603")
      (libsource (lib "eagle-import") (part "10UF-0603-6.3V-20%"))
    )
    (comp (ref "C58")
      (value "0.1uF")
      (footprint "eagle-import:0603")
      (libsource (lib "eagle-import") (part "0.1UF-0603-25V-5%"))
    )
    (comp (ref "C59")
      (value "0.1uF")
      (footprint "eagle-import:0603")
      (libsource (lib "eagle-import") (part "0.1UF-0603-25V-5%"))
    )
    (comp (ref "C60")
      (value "2.2uF")
      (footprint "eagle-import:0603")
      (libsource (lib "eagle-import") (part "2.2UF-0603-10V-20%"))
    )
    (comp (ref "C61")
      (value "2.2uF")
      (footprint "eagle-import:0603")
      (libsource (lib "eagle-import") (part "2.2UF-0603-10V-20%"))
    )
    (comp (ref "C62")
      (value "0.1uF")
      (footprint "eagle-import:0603")
      (libsource (lib "eagle-import") (part "0.1UF-0603-25V-5%"))
    )
    (comp (ref "COM2_CTS")
      (value "TEST-POINTPOGO_PTH")
      (footprint "eagle-import:1X01_NO_SILK")
      (libsource (lib "eagle-import") (part "TEST-POINTPOGO_PTH"))
    )
    (comp (ref "COM2_RTS")
      (value "TEST-POINTPOGO_PTH")
      (footprint "eagle-import:1X01_NO_SILK")
      (libsource (lib "eagle-import") (part "TEST-POINTPOGO_PTH"))
    )
    (comp (ref "COM2_RX")
      (value "TEST-POINTPOGO_PTH")
      (footprint "eagle-import:1X01_NO_SILK")
      (libsource (lib "eagle-import") (part "TEST-POINTPOGO_PTH"))
    )
    (comp (ref "COM2_TX")
      (value "TEST-POINTPOGO_PTH")
      (footprint "eagle-import:1X01_NO_SILK")
      (libsource (lib "eagle-import") (part "TEST-POINTPOGO_PTH"))
    )
    (comp (ref "COM3_CTS")
      (value "TEST-POINTPOGO_PTH")
      (footprint "eagle-import:1X01_NO_SILK")
      (libsource (lib "eagle-import") (part "TEST-POINTPOGO_PTH"))
    )
    (comp (ref "COM3_RTS")
      (value "TEST-POINTPOGO_PTH")
      (footprint "eagle-import:1X01_NO_SILK")
      (libsource (lib "eagle-import") (part "TEST-POINTPOGO_PTH"))
    )
    (comp (ref "COM3_RX")
      (value "TEST-POINTPOGO_PTH")
      (footprint "eagle-import:1X01_NO_SILK")
      (libsource (lib "eagle-import") (part "TEST-POINTPOGO_PTH"))
    )
    (comp (ref "COM3_TX")
      (value "TEST-POINTPOGO_PTH")
      (footprint "eagle-import:1X01_NO_SILK")
      (libsource (lib "eagle-import") (part "TEST-POINTPOGO_PTH"))
    )
    (comp (ref "D1")
      (value "ESD Diode")
      (footprint "eagle-import:SOT-23-6")
      (libsource (lib "eagle-import") (part "TVS_DIODE_ARRAY_DT1042-04SO-7"))
    )
    (comp (ref "D8")
      (value "ESD Diode")
      (footprint "eagle-import:SOT-23-6")
      (libsource (lib "eagle-import") (part "TVS_DIODE_ARRAY_DT1042-04SO-7"))
    )
    (comp (ref "D17")
      (value "PESD0402")
      (footprint "eagle-import:0402")
      (fields
        (field (name "DIGIKEY_PART") "PESD0402-140CT-ND")
        (field (name "MOUSE_PART") "650-PESD0402-140")
      )
      (libsource (lib "eagle-import") (part "PESD0402-0402"))
    )
    (comp (ref "FB1")
      (value "470Ω")
      (footprint "eagle-import:0603")
      (libsource (lib "eagle-import") (part "FERRITE_BEAD-0603-470Ω-100MHZ-1A-200MILIΩ"))
    )
    (comp (ref "FB3")
      (value "470Ω")
      (footprint "eagle-import:0603")
      (libsource (lib "eagle-import") (part "FERRITE_BEAD-0603-470Ω-100MHZ-1A-200MILIΩ"))
    )
    (comp (ref "FRAME3")
      (value "FRAME-LEDGERNO_FOOTPRINT")
      (footprint "eagle-import:DUMMY")
      (fields (field (name "DESIGNER") "Paul Clark") (field (name "REV") "V01"))
      (libsource (lib "eagle-import") (part "FRAME-LEDGERNO_FOOTPRINT"))
    )
    (comp (ref "GPIO_1")
      (value "TEST-POINTPOGO_PTH")
      (footprint "eagle-import:1X01_NO_SILK")
      (libsource (lib "eagle-import") (part "TEST-POINTPOGO_PTH"))
    )
    (comp (ref "GPIO_2")
      (value "TEST-POINTPOGO_PTH")
      (footprint "eagle-import:1X01_NO_SILK")
      (libsource (lib "eagle-import") (part "TEST-POINTPOGO_PTH"))
    )
    (comp (ref "J2")
      (value "MAGJACK-POE")
      (footprint "eagle-import:MAGJACK-SYM_LED")
      (libsource (lib "eagle-import") (part "MAGJACK-POE"))
    )
    (comp (ref "J3")
      (value "MICRO-SD-PUSH-PUSH-EXT-PIN")
      (footprint "eagle-import:MICROSD-EXTERNALPIN")
      (libsource (lib "eagle-import") (part "MICRO-SD-PUSH-PUSH-EXT-PIN"))
    )
    (comp (ref "J5")
      (value "CONN_10_3.5MM_RA_HEADER")
      (footprint "eagle-import:1X10_SCREW_TERMINAL_3.5MM")
      (libsource (lib "eagle-import") (part "CONN_10_3.5MM_RA_HEADER"))
    )
    (comp (ref "J6")
      (value "USB_C_4-LAYER_PADS")
      (footprint "eagle-import:USB-C-16P_4LAYER-PADS")
      (libsource (lib "eagle-import") (part "USB_C_4-LAYER_PADS"))
    )
    (comp (ref "LINK2")
      (value "JUMPER-SMT_2_NC_TRACE_SILK")
      (footprint "eagle-import:SMT-JUMPER_2_NC_TRACE_SILK")
      (libsource (lib "eagle-import") (part "JUMPER-SMT_2_NC_TRACE_SILK"))
    )
    (comp (ref "MOSAIC_RF")
      (value "ANTENNA-SMA-GROUNDEDEDGE_SMA")
      (footprint "eagle-import:SMA-EDGE")
      (libsource (lib "eagle-import") (part "ANTENNA-SMA-GROUNDEDEDGE_SMA"))
    )
    (comp (ref "R6")
      (value "1k")
      (footprint "eagle-import:0603")
      (libsource (lib "eagle-import") (part "1KOHM-0603-1/10W-1%"))
    )
    (comp (ref "R7")
      (value "1k")
      (footprint "eagle-import:0603")
      (libsource (lib "eagle-import") (part "1KOHM-0603-1/10W-1%"))
    )
    (comp (ref "R8")
      (value "49.9")
      (footprint "eagle-import:0603")
      (libsource (lib "eagle-import") (part "49.9OHM-0603-1/10W-1%"))
    )
    (comp (ref "R9")
      (value "49.9")
      (footprint "eagle-import:0603")
      (libsource (lib "eagle-import") (part "49.9OHM-0603-1/10W-1%"))
    )
    (comp (ref "R10")
      (value "49.9")
      (footprint "eagle-import:0603")
      (libsource (lib "eagle-import") (part "49.9OHM-0603-1/10W-1%"))
    )
    (comp (ref "R12")
      (value "49.9")
      (footprint "eagle-import:0603")
      (libsource (lib "eagle-import") (part "49.9OHM-0603-1/10W-1%"))
    )
    (comp (ref "R13")
      (value "13k")
      (footprint "eagle-import:0603")
      (libsource (lib "eagle-import") (part "13KOHM-0603-1/10W-1%"))
    )
    (comp (ref "R14")
      (value "13k")
      (footprint "eagle-import:0603")
      (libsource (lib "eagle-import") (part "13KOHM-0603-1/10W-1%"))
    )
    (comp (ref "R15")
      (value "10k")
      (footprint "eagle-import:0603")
      (libsource (lib "eagle-import") (part "10KOHM-0603-1/10W-1%"))
    )
    (comp (ref "R17")
      (value "10k")
      (footprint "eagle-import:0603")
      (libsource (lib "eagle-import") (part "10KOHM-0603-1/10W-1%"))
    )
    (comp (ref "R18")
      (value "10k")
      (footprint "eagle-import:0603")
      (libsource (lib "eagle-import") (part "10KOHM-0603-1/10W-1%"))
    )
    (comp (ref "R20")
      (value "4.7k")
      (footprint "eagle-import:0603")
      (libsource (lib "eagle-import") (part "4.7KOHM-0603-1/10W-1%"))
    )
    (comp (ref "R22")
      (value "10k")
      (footprint "eagle-import:0603")
      (libsource (lib "eagle-import") (part "10KOHM-0603-1/10W-1%"))
    )
    (comp (ref "R23")
      (value "10k")
      (footprint "eagle-import:0603")
      (libsource (lib "eagle-import") (part "10KOHM-0603-1/10W-1%"))
    )
    (comp (ref "R33")
      (value "5.1k")
      (footprint "eagle-import:0603")
      (libsource (lib "eagle-import") (part "5.1KOHM5.1KOHM-0603-1/10W-1%"))
    )
    (comp (ref "R34")
      (value "5.1k")
      (footprint "eagle-import:0603")
      (libsource (lib "eagle-import") (part "5.1KOHM5.1KOHM-0603-1/10W-1%"))
    )
    (comp (ref "R43")
      (value "10k")
      (footprint "eagle-import:0603")
      (libsource (lib "eagle-import") (part "10KOHM-0603-1/10W-1%"))
    )
    (comp (ref "R44")
      (value "10k")
      (footprint "eagle-import:0603")
      (libsource (lib "eagle-import") (part "10KOHM-0603-1/10W-1%"))
    )
    (comp (ref "R46")
      (value "10k")
      (footprint "eagle-import:0603")
      (libsource (lib "eagle-import") (part "10KOHM-0603-1/10W-1%"))
    )
    (comp (ref "R47")
      (value "10k")
      (footprint "eagle-import:0603")
      (libsource (lib "eagle-import") (part "10KOHM-0603-1/10W-1%"))
    )
    (comp (ref "RDY")
      (value "TEST-POINTPOGO_PTH")
      (footprint "eagle-import:1X01_NO_SILK")
      (libsource (lib "eagle-import") (part "TEST-POINTPOGO_PTH"))
    )
    (comp (ref "REF")
      (value "TEST-POINTPOGO_PTH")
      (footprint "eagle-import:1X01_NO_SILK")
      (libsource (lib "eagle-import") (part "TEST-POINTPOGO_PTH"))
    )
    (comp (ref "SHLD2")
      (value "JUMPER-SMT_2_NC_TRACE_SILK")
      (footprint "eagle-import:SMT-JUMPER_2_NC_TRACE_SILK")
      (libsource (lib "eagle-import") (part "JUMPER-SMT_2_NC_TRACE_SILK"))
    )
    (comp (ref "U4")
      (value "TXS0108")
      (footprint "eagle-import:VFQFN-20")
      (libsource (lib "eagle-import") (part "TXS0108-VFQFN_20"))
    )
    (comp (ref "U8")
      (value "MOSAIC-X5X5")
      (footprint "eagle-import:MOSAIC_LGA")
      (libsource (lib "eagle-import") (part "MOSAIC-X5X5"))
    )
    (comp (ref "U9")
      (value "KSZ8041NL")
      (footprint "eagle-import:MLF55Q-32LD")
      (libsource (lib "eagle-import") (part "KSZ8041NL"))
    )
    (comp (ref "U11")
      (value "SN74AVC4T774PW")
      (footprint "eagle-import:SOP65P640X120-16N")
      (libsource (lib "eagle-import") (part "SN74AVC4T774PW"))
    )
    (comp (ref "VDDA")
      (value "TEST-POINTPOGO_PTH")
      (footprint "eagle-import:1X01_NO_SILK")
      (libsource (lib "eagle-import") (part "TEST-POINTPOGO_PTH"))
    )
    (comp (ref "VUSB2")
      (value "TEST-POINTPOGO_PTH")
      (footprint "eagle-import:1X01_NO_SILK")
      (libsource (lib "eagle-import") (part "TEST-POINTPOGO_PTH"))
    )
  )
  (nets
    (net (code "1") (name "1.8V") (class "Default")
      (node (ref "1V8") (pin "1") (pinfunction "1_1") (pintype "bidirectional"))
      (node (ref "C60") (pin "1") (pinfunction "1_1") (pintype "passive"))
      (node (ref "C62") (pin "1") (pinfunction "1_1") (pintype "passive"))
      (node (ref "R18") (pin "2") (pinfunction "2_2") (pintype "passive"))
      (node (ref "U11") (pin "16") (pinfunction "VCCA_16") (pintype "power_in"))
      (node (ref "U11") (pin "6") (pinfunction "A4_6") (pintype "bidirectional"))
      (node (ref "U11") (pin "7") (pinfunction "DIR3_7") (pintype "input"))
      (node (ref "U11") (pin "8") (pinfunction "DIR4_8") (pintype "input"))
      (node (ref "U8") (pin "AC4") (pinfunction "1V8_OUT_AC4") (pintype "output"))
    )
    (net (code "2") (name "3.3V") (class "Default")
      (node (ref "3V3") (pin "1") (pinfunction "1_1") (pintype "bidirectional"))
      (node (ref "C1") (pin "1") (pinfunction "1_1") (pintype "passive"))
      (node (ref "C14") (pin "1") (pinfunction "1_1") (pintype "passive"))
      (node (ref "C15") (pin "1") (pinfunction "1_1") (pintype "passive"))
      (node (ref "C2") (pin "1") (pinfunction "1_1") (pintype "passive"))
      (node (ref "C21") (pin "1") (pinfunction "1_1") (pintype "passive"))
      (node (ref "C3") (pin "1") (pinfunction "1_1") (pintype "passive"))
      (node (ref "C32") (pin "1") (pinfunction "1_1") (pintype "passive"))
      (node (ref "C4") (pin "1") (pinfunction "1_1") (pintype "passive"))
      (node (ref "C41") (pin "1") (pinfunction "1_1") (pintype "passive"))
      (node (ref "C56") (pin "1") (pinfunction "1_1") (pintype "passive"))
      (node (ref "FB2") (pin "1") (pinfunction "1_1") (pintype "passive"))
      (node (ref "I2C") (pin "2") (pinfunction "2_2") (pintype "passive"))
      (node (ref "J4") (pin "2") (pinfunction "2_2") (pintype "power_in"))
      (node (ref "J9") (pin "11") (pinfunction "YLW+_11") (pintype "bidirectional"))
      (node (ref "J9") (pin "13") (pinfunction "GRN+_13") (pintype "bidirectional"))
      (node (ref "R16") (pin "2") (pinfunction "2_2") (pintype "passive"))
      (node (ref "R21") (pin "2") (pinfunction "2_2") (pintype "passive"))
      (node (ref "R29") (pin "2") (pinfunction "2_2") (pintype "passive"))
      (node (ref "R3") (pin "2") (pinfunction "2_2") (pintype "passive"))
      (node (ref "R49") (pin "2") (pinfunction "2_2") (pintype "passive"))
      (node (ref "U1") (pin "2") (pinfunction "3V3_2") (pintype "bidirectional"))
      (node (ref "U2") (pin "16") (pinfunction "VCC_16") (pintype "bidirectional"))
      (node (ref "U2") (pin "4") (pinfunction "V3_4") (pintype "bidirectional"))
      (node (ref "U5") (pin "10") (pinfunction "OE_10") (pintype "bidirectional"))
      (node (ref "U5") (pin "2") (pinfunction "VCCA_2") (pintype "bidirectional"))
      (node (ref "U6") (pin "5") (pinfunction "OUT_5") (pintype "passive"))
      (node (ref "U7") (pin "17") (pinfunction "VDDIO_17") (pintype "power_in"))
      (node (ref "VCCIO") (pin "1") (pinfunction "O_1") (pintype "passive"))
    )
    (net (code "3") (name "3.3V_SW") (class "Default")
      (node (ref "3V3_SW") (pin "1") (pinfunction "1_1") (pintype "bidirectional"))
      (node (ref "C11") (pin "1") (pinfunction "1_1") (pintype "passive"))
      (node (ref "C18") (pin "1") (pinfunction "1_1") (pintype "passive"))
      (node (ref "C19") (pin "1") (pinfunction "1_1") (pintype "passive"))
      (node (ref "C20") (pin "1") (pinfunction "1_1") (pintype "passive"))
      (node (ref "C46") (pin "1") (pinfunction "1_1") (pintype "passive"))
      (node (ref "C5") (pin "1") (pinfunction "1_1") (pintype "passive"))
      (node (ref "C53") (pin "1") (pinfunction "1_1") (pintype "passive"))
      (node (ref "C54") (pin "1") (pinfunction "1_1") (pintype "passive"))
      (node (ref "C58") (pin "1") (pinfunction "1_1") (pintype "passive"))
      (node (ref "C6") (pin "1") (pinfunction "1_1") (pintype "passive"))
      (node (ref "C7") (pin "1") (pinfunction "1_1") (pintype "passive"))
      (node (ref "FB1") (pin "1") (pinfunction "1_1") (pintype "passive"))
      (node (ref "J2") (pin "11") (pinfunction "YLW+_11") (pintype "bidirectional"))
      (node (ref "J2") (pin "13") (pinfunction "GRN+_13") (pintype "bidirectional"))
      (node (ref "J3") (pin "4") (pinfunction "VCC_4") (pintype "bidirectional"))
      (node (ref "R15") (pin "2") (pinfunction "2_2") (pintype "passive"))
      (node (ref "R17") (pin "2") (pinfunction "2_2") (pintype "passive"))
      (node (ref "R20") (pin "2") (pinfunction "2_2") (pintype "passive"))
      (node (ref "R22") (pin "1") (pinfunction "1_1") (pintype "passive"))
      (node (ref "R46") (pin "2") (pinfunction "2_2") (pintype "passive"))
      (node (ref "R47") (pin "2") (pinfunction "2_2") (pintype "passive"))
      (node (ref "U11") (pin "15") (pinfunction "VCCB_15") (pintype "power_in"))
      (node (ref "U3") (pin "5") (pinfunction "OUT_5") (pintype "passive"))
      (node (ref "U4") (pin "10") (pinfunction "OE_10") (pintype "bidirectional"))
      (node (ref "U4") (pin "2") (pinfunction "VCCA_2") (pintype "bidirectional"))
      (node (ref "U8") (pin "A18") (pinfunction "VDD_3V3_A18") (pintype "input"))
      (node (ref "U8") (pin "A19") (pinfunction "VDD_3V3_A19") (pintype "input"))
      (node (ref "U8") (pin "A20") (pinfunction "VDD_3V3_A20") (pintype "input"))
      (node (ref "U8") (pin "B18") (pinfunction "VDD_3V3_B18") (pintype "input"))
      (node (ref "U8") (pin "B19") (pinfunction "VDD_3V3_B19") (pintype "input"))
      (node (ref "U8") (pin "B20") (pinfunction "VDD_3V3_B20") (pintype "input"))
      (node (ref "U8") (pin "B8") (pinfunction "VDD_BAT_B8") (pintype "input"))
      (node (ref "U8") (pin "C18") (pinfunction "VDD_3V3_C18") (pintype "input"))
      (node (ref "U8") (pin "C19") (pinfunction "VDD_3V3_C19") (pintype "input"))
      (node (ref "U8") (pin "C20") (pinfunction "VDD_3V3_C20") (pintype "input"))
      (node (ref "U9") (pin "17") (pinfunction "VDDIO_17") (pintype "power_in"))
    )
    (net (code "4") (name "5V") (class "Default")
      (node (ref "5V") (pin "1") (pinfunction "1_1") (pintype "bidirectional"))
      (node (ref "C10") (pin "1") (pinfunction "1_1") (pintype "passive"))
      (node (ref "C17") (pin "1") (pinfunction "1_1") (pintype "passive"))
      (node (ref "C57") (pin "+") (pinfunction "+_+") (pintype "passive"))
      (node (ref "C61") (pin "1") (pinfunction "1_1") (pintype "passive"))
      (node (ref "C8") (pin "1") (pinfunction "1_1") (pintype "passive"))
      (node (ref "C9") (pin "1") (pinfunction "1_1") (pintype "passive"))
      (node (ref "F1") (pin "1") (pinfunction "1_1") (pintype "bidirectional"))
      (node (ref "FB3") (pin "1") (pinfunction "1_1") (pintype "passive"))
      (node (ref "U3") (pin "1") (pinfunction "IN_1") (pintype "input"))
      (node (ref "U3") (pin "3") (pinfunction "EN_3") (pintype "input"))
      (node (ref "U6") (pin "1") (pinfunction "IN_1") (pintype "input"))
      (node (ref "U6") (pin "3") (pinfunction "EN_3") (pintype "input"))
      (node (ref "U8") (pin "A8") (pinfunction "V_USB_A8") (pintype "input"))
      (node (ref "VCCIO") (pin "3") (pinfunction "S_3") (pintype "passive"))
    )
    (net (code "5") (name "ACT_ESP32") (class "Default")
      (node (ref "R26") (pin "2") (pinfunction "2_2") (pintype "passive"))
      (node (ref "U7") (pin "31") (pinfunction "LED1/SPEED_31") (pintype "output"))
    )
    (net (code "6") (name "ACT_MOSAIC") (class "Default")
      (node (ref "R7") (pin "2") (pinfunction "2_2") (pintype "passive"))
      (node (ref "U9") (pin "31") (pinfunction "LED1/SPEED_31") (pintype "output"))
    )
    (net (code "7") (name "CH340-DTR") (class "Default")
      (node (ref "DTR") (pin "1") (pinfunction "1_1") (pintype "bidirectional"))
      (node (ref "Q1") (pin "1") (pinfunction "E_1") (pintype "passive"))
      (node (ref "R4") (pin "2") (pinfunction "2_2") (pintype "passive"))
      (node (ref "U2") (pin "13") (pinfunction "~{DTR}_13") (pintype "bidirectional"))
    )
    (net (code "8") (name "CH340-RTS") (class "Default")
      (node (ref "Q1") (pin "4") (pinfunction "E_4") (pintype "passive"))
      (node (ref "R5") (pin "2") (pinfunction "2_2") (pintype "passive"))
      (node (ref "RTS") (pin "1") (pinfunction "1_1") (pintype "bidirectional"))
      (node (ref "U2") (pin "14") (pinfunction "~{RTS}_14") (pintype "bidirectional"))
    )
    (net (code "9") (name "CH340-RXI") (class "Default")
      (node (ref "TX") (pin "1") (pinfunction "1_1") (pintype "bidirectional"))
      (node (ref "U1") (pin "35") (pinfunction "TX-IO1_35") (pintype "bidirectional"))
      (node (ref "U2") (pin "3") (pinfunction "RXI_3") (pintype "bidirectional"))
    )
    (net (code "10") (name "CH340-TXO") (class "Default")
      (node (ref "RX") (pin "1") (pinfunction "1_1") (pintype "bidirectional"))
      (node (ref "U1") (pin "34") (pinfunction "RX-IO3_34") (pintype "bidirectional"))
      (node (ref "U2") (pin "2") (pinfunction "TXO_2") (pintype "bidirectional"))
    )
    (net (code "11") (name "COM4_RX") (class "Default")
      (node (ref "R52") (pin "2") (pinfunction "2_2") (pintype "passive"))
      (node (ref "U8") (pin "D3") (pinfunction "COM4_RX_D3") (pintype "input"))
    )
    (net (code "12") (name "COM4_TX") (class "Default")
      (node (ref "R51") (pin "2") (pinfunction "2_2") (pintype "passive"))
      (node (ref "U8") (pin "E3") (pinfunction "COM4_TX_E3") (pintype "output"))
    )
    (net (code "13") (name "D+_ESP32") (class "Default")
      (node (ref "D10") (pin "1") (pinfunction "IO1_1") (pintype "bidirectional"))
      (node (ref "J1") (pin "A6") (pinfunction "D+_A6") (pintype "bidirectional"))
      (node (ref "J1") (pin "B6") (pinfunction "D+_B6") (pintype "bidirectional"))
      (node (ref "U2") (pin "5") (pinfunction "UD+_5") (pintype "bidirectional"))
    )
    (net (code "14") (name "D+_MOSAIC") (class "Default")
      (node (ref "D8") (pin "1") (pinfunction "IO1_1") (pintype "bidirectional"))
      (node (ref "J6") (pin "A6") (pinfunction "D+_A6") (pintype "bidirectional"))
      (node (ref "J6") (pin "B6") (pinfunction "D+_B6") (pintype "bidirectional"))
      (node (ref "U8") (pin "A5") (pinfunction "USB_D+_A5") (pintype "bidirectional"))
    )
    (net (code "15") (name "D-_ESP32") (class "Default")
      (node (ref "D10") (pin "3") (pinfunction "IO2_3") (pintype "bidirectional"))
      (node (ref "J1") (pin "A7") (pinfunction "D-_A7") (pintype "bidirectional"))
      (node (ref "J1") (pin "B7") (pinfunction "D-_B7") (pintype "bidirectional"))
      (node (ref "U2") (pin "6") (pinfunction "UD-_6") (pintype "bidirectional"))
    )
    (net (code "16") (name "D-_MOSAIC") (class "Default")
      (node (ref "D8") (pin "3") (pinfunction "IO2_3") (pintype "bidirectional"))
      (node (ref "J6") (pin "A7") (pinfunction "D-_A7") (pintype "bidirectional"))
      (node (ref "J6") (pin "B7") (pinfunction "D-_B7") (pintype "bidirectional"))
      (node (ref "U8") (pin "A6") (pinfunction "USB_D-_A6") (pintype "bidirectional"))
    )
    (net (code "17") (name "ESP2_TX") (class "Default")
      (node (ref "R48") (pin "1") (pinfunction "1_1") (pintype "passive"))
      (node (ref "R52") (pin "1") (pinfunction "1_1") (pintype "passive"))
      (node (ref "U1") (pin "24") (pinfunction "IOA2_24") (pintype "bidirectional"))
    )
    (net (code "18") (name "ESP4_RX") (class "Default")
      (node (ref "R51") (pin "1") (pinfunction "1_1") (pintype "passive"))
      (node (ref "U1") (pin "26") (pinfunction "IOA4_26") (pintype "bidirectional"))
    )
    (net (code "19") (name "ESP5_ERST") (class "Default")
      (node (ref "R49") (pin "1") (pinfunction "1_1") (pintype "passive"))
      (node (ref "U1") (pin "29") (pinfunction "CS3/IO5_29") (pintype "bidirectional"))
      (node (ref "U7") (pin "32") (pinfunction "~{RST}_32") (pintype "bidirectional"))
    )
    (net (code "20") (name "ESP12_LED_WIFI") (class "Default")
      (node (ref "R28") (pin "1") (pinfunction "1_1") (pintype "passive"))
      (node (ref "R50") (pin "1") (pinfunction "1_1") (pintype "passive"))
      (node (ref "U1") (pin "14") (pinfunction "POCI2/IOA12_14") (pintype "bidirectional"))
    )
    (net (code "21") (name "ESP14_SCL") (class "Default")
      (node (ref "J4") (pin "4") (pinfunction "4_4") (pintype "passive"))
      (node (ref "R_SCL") (pin "1") (pinfunction "1_1") (pintype "passive"))
      (node (ref "SCL2") (pin "1") (pinfunction "1_1") (pintype "bidirectional"))
      (node (ref "U1") (pin "13") (pinfunction "SCK2/IOA14_13") (pintype "bidirectional"))
      (node (ref "U5") (pin "6") (pinfunction "A5_6") (pintype "bidirectional"))
    )
    (net (code "22") (name "ESP14_SCL_IO") (class "Default")
      (node (ref "J13") (pin "4") (pinfunction "4_4") (pintype "passive"))
      (node (ref "U5") (pin "15") (pinfunction "B5_15") (pintype "bidirectional"))
    )
    (net (code "23") (name "ESP15_LED_BT") (class "Default")
      (node (ref "R36") (pin "1") (pinfunction "1_1") (pintype "passive"))
      (node (ref "U1") (pin "16") (pinfunction "PICO2/IOA13_16") (pintype "bidirectional"))
    )
    (net (code "24") (name "ESP15_SDA") (class "Default")
      (node (ref "J4") (pin "3") (pinfunction "3_3") (pintype "passive"))
      (node (ref "R_SDA") (pin "1") (pinfunction "1_1") (pintype "passive"))
      (node (ref "SDA2") (pin "1") (pinfunction "1_1") (pintype "bidirectional"))
      (node (ref "U1") (pin "23") (pinfunction "CS2/IOA15_23") (pintype "bidirectional"))
      (node (ref "U5") (pin "7") (pinfunction "A6_7") (pintype "bidirectional"))
    )
    (net (code "25") (name "ESP15_SDA_IO") (class "Default")
      (node (ref "J13") (pin "3") (pinfunction "3_3") (pintype "passive"))
      (node (ref "U5") (pin "14") (pinfunction "B6_14") (pintype "bidirectional"))
    )
    (net (code "26") (name "ESP18_MDIO") (class "Default")
      (node (ref "R21") (pin "1") (pinfunction "1_1") (pintype "passive"))
      (node (ref "U1") (pin "30") (pinfunction "SCK3/IO18_30") (pintype "bidirectional"))
      (node (ref "U7") (pin "11") (pinfunction "MDIO_11") (pintype "bidirectional"))
    )
    (net (code "27") (name "ESP19_TXD0") (class "Default")
      (node (ref "U1") (pin "31") (pinfunction "POCI3/IO19_31") (pintype "bidirectional"))
      (node (ref "U7") (pin "24") (pinfunction "TXD0_24") (pintype "bidirectional"))
    )
    (net (code "28") (name "ESP21_TXEN") (class "Default")
      (node (ref "U1") (pin "33") (pinfunction "SDA/IO21_33") (pintype "bidirectional"))
      (node (ref "U7") (pin "23") (pinfunction "TXEN_23") (pintype "bidirectional"))
    )
    (net (code "29") (name "ESP22_TXD1") (class "Default")
      (node (ref "U1") (pin "36") (pinfunction "SCL/IO22_36") (pintype "bidirectional"))
      (node (ref "U7") (pin "25") (pinfunction "TXD1_25") (pintype "bidirectional"))
    )
    (net (code "30") (name "ESP23_MDC") (class "Default")
      (node (ref "U1") (pin "37") (pinfunction "PICO3/IO23_37") (pintype "bidirectional"))
      (node (ref "U7") (pin "12") (pinfunction "MDC_12") (pintype "bidirectional"))
    )
    (net (code "31") (name "ESP25_RXD0") (class "Default")
      (node (ref "R30") (pin "1") (pinfunction "1_1") (pintype "passive"))
      (node (ref "U1") (pin "10") (pinfunction "DAC1/IOA25_10") (pintype "bidirectional"))
    )
    (net (code "32") (name "ESP26_RXD1") (class "Default")
      (node (ref "R31") (pin "1") (pinfunction "1_1") (pintype "passive"))
      (node (ref "U1") (pin "11") (pinfunction "DAC2/IOA26_11") (pintype "bidirectional"))
    )
    (net (code "33") (name "ESP27_CRSDV") (class "Default")
      (node (ref "R32") (pin "1") (pinfunction "1_1") (pintype "passive"))
      (node (ref "U1") (pin "12") (pinfunction "IOA27_12") (pintype "bidirectional"))
    )
    (net (code "34") (name "ESP32_TX") (class "Default")
      (node (ref "U1") (pin "8") (pinfunction "XTAL_P/IOA32_8") (pintype "bidirectional"))
      (node (ref "U5") (pin "3") (pinfunction "A2_3") (pintype "bidirectional"))
    )
    (net (code "35") (name "ESP32_TX_IO") (class "Default")
      (node (ref "J13") (pin "7") (pinfunction "7_7") (pintype "passive"))
      (node (ref "U5") (pin "18") (pinfunction "B2_18") (pintype "bidirectional"))
    )
    (net (code "36") (name "ESP33_RTS") (class "Default")
      (node (ref "U1") (pin "9") (pinfunction "XTAL_N/IOA33_9") (pintype "bidirectional"))
      (node (ref "U5") (pin "4") (pinfunction "A3_4") (pintype "bidirectional"))
    )
    (net (code "37") (name "ESP33_RTS_IO") (class "Default")
      (node (ref "J13") (pin "6") (pinfunction "6_6") (pintype "passive"))
      (node (ref "U5") (pin "17") (pinfunction "B3_17") (pintype "bidirectional"))
    )
    (net (code "38") (name "ESP34_RX") (class "Default")
      (node (ref "U1") (pin "6") (pinfunction "IA34_6") (pintype "bidirectional"))
      (node (ref "U5") (pin "1") (pinfunction "A1_1") (pintype "bidirectional"))
    )
    (net (code "39") (name "ESP34_RX_IO") (class "Default")
      (node (ref "J13") (pin "8") (pinfunction "8_8") (pintype "passive"))
      (node (ref "U5") (pin "20") (pinfunction "B1_20") (pintype "bidirectional"))
    )
    (net (code "40") (name "ESP35_CTS") (class "Default")
      (node (ref "U1") (pin "7") (pinfunction "IA35_7") (pintype "bidirectional"))
      (node (ref "U5") (pin "5") (pinfunction "A4_5") (pintype "bidirectional"))
    )
    (net (code "41") (name "ESP35_CTS_IO") (class "Default")
      (node (ref "J13") (pin "5") (pinfunction "5_5") (pintype "passive"))
      (node (ref "U5") (pin "16") (pinfunction "B4_16") (pintype "bidirectional"))
    )
    (net (code "42") (name "ESP_REFCLK") (class "Default")
      (node (ref "R19") (pin "1") (pinfunction "1_1") (pintype "passive"))
      (node (ref "U1") (pin "25") (pinfunction "IOA0_25") (pintype "bidirectional"))
      (node (ref "U7") (pin "9") (pinfunction "XI/REFCLK_9") (pintype "bidirectional"))
    )
    (net (code "43") (name "ETHER_CLK") (class "Default")
      (node (ref "U8") (pin "AA2") (pinfunction "ETHER_CLK_AA2") (pintype "output"))
      (node (ref "U9") (pin "9") (pinfunction "XI/REFCLK_9") (pintype "bidirectional"))
    )
    (net (code "44") (name "ETHER_CRSDV") (class "Default")
      (node (ref "U8") (pin "N2") (pinfunction "ETHER_CRSDV_N2") (pintype "input"))
      (node (ref "U9") (pin "18") (pinfunction "RXDV/CONFIG2_18") (pintype "bidirectional"))
    )
    (net (code "45") (name "ETHER_MDC") (class "Default")
      (node (ref "U8") (pin "V2") (pinfunction "ETHER_MDC_V2") (pintype "output"))
      (node (ref "U9") (pin "12") (pinfunction "MDC_12") (pintype "bidirectional"))
    )
    (net (code "46") (name "ETHER_MDIO") (class "Default")
      (node (ref "R20") (pin "1") (pinfunction "1_1") (pintype "passive"))
      (node (ref "U8") (pin "W2") (pinfunction "ETHER_MDIO_W2") (pintype "bidirectional"))
      (node (ref "U9") (pin "11") (pinfunction "MDIO_11") (pintype "bidirectional"))
    )
    (net (code "47") (name "ETHER_RXD0") (class "Default")
      (node (ref "U8") (pin "R2") (pinfunction "ETHER_RXD0_R2") (pintype "input"))
      (node (ref "U9") (pin "16") (pinfunction "RXD0/DUPLEX_16") (pintype "bidirectional"))
    )
    (net (code "48") (name "ETHER_RXD1") (class "Default")
      (node (ref "U8") (pin "T2") (pinfunction "ETHER_RXD1_T2") (pintype "input"))
      (node (ref "U9") (pin "15") (pinfunction "RXD1/PHYAD2_15") (pintype "bidirectional"))
    )
    (net (code "49") (name "ETHER_RXER") (class "Default")
      (node (ref "U8") (pin "M2") (pinfunction "ETHER_RXER_M2") (pintype "input"))
      (node (ref "U9") (pin "20") (pinfunction "RXER/ISO_20") (pintype "bidirectional"))
    )
    (net (code "50") (name "ETHER_TXD0") (class "Default")
      (node (ref "U8") (pin "J2") (pinfunction "ETHER_TXD0_J2") (pintype "output"))
      (node (ref "U9") (pin "24") (pinfunction "TXD0_24") (pintype "bidirectional"))
    )
    (net (code "51") (name "ETHER_TXD1") (class "Default")
      (node (ref "U8") (pin "H2") (pinfunction "ETHER_TXD1_H2") (pintype "output"))
      (node (ref "U9") (pin "25") (pinfunction "TXD1_25") (pintype "bidirectional"))
    )
    (net (code "52") (name "ETHER_TXEN") (class "Default")
      (node (ref "U8") (pin "L2") (pinfunction "ETHER_TXEN_L2") (pintype "output"))
      (node (ref "U9") (pin "23") (pinfunction "TXEN_23") (pintype "bidirectional"))
    )
    (net (code "53") (name "ETHER_~{RST}") (class "Default")
      (node (ref "R22") (pin "2") (pinfunction "2_2") (pintype "passive"))
      (node (ref "U8") (pin "F2") (pinfunction "ETHER_~{RST}_F2") (pintype "input"))
      (node (ref "U9") (pin "32") (pinfunction "~{RST}_32") (pintype "bidirectional"))
    )
    (net (code "54") (name "GND") (class "Default")
      (node (ref "BOOT") (pin "1") (pinfunction "1_1") (pintype "passive"))
      (node (ref "C1") (pin "2") (pinfunction "2_2") (pintype "passive"))
      (node (ref "C10") (pin "2") (pinfunction "2_2") (pintype "passive"))
      (node (ref "C11") (pin "2") (pinfunction "2_2") (pintype "passive"))
      (node (ref "C13") (pin "2") (pinfunction "2_2") (pintype "passive"))
      (node (ref "C14") (pin "2") (pinfunction "2_2") (pintype "passive"))
      (node (ref "C15") (pin "2") (pinfunction "2_2") (pintype "passive"))
      (node (ref "C16") (pin "-") (pinfunction "-_-") (pintype "passive"))
      (node (ref "C17") (pin "2") (pinfunction "2_2") (pintype "passive"))
      (node (ref "C18") (pin "2") (pinfunction "2_2") (pintype "passive"))
      (node (ref "C19") (pin "2") (pinfunction "2_2") (pintype "passive"))
      (node (ref "C2") (pin "2") (pinfunction "2_2") (pintype "passive"))
      (node (ref "C20") (pin "2") (pinfunction "2_2") (pintype "passive"))
      (node (ref "C21") (pin "2") (pinfunction "2_2") (pintype "passive"))
      (node (ref "C22") (pin "2") (pinfunction "2_2") (pintype "passive"))
      (node (ref "C23") (pin "2") (pinfunction "2_2") (pintype "passive"))
      (node (ref "C24") (pin "2") (pinfunction "2_2") (pintype "passive"))
      (node (ref "C25") (pin "2") (pinfunction "2_2") (pintype "passive"))
      (node (ref "C26") (pin "2") (pinfunction "2_2") (pintype "passive"))
      (node (ref "C27") (pin "2") (pinfunction "2_2") (pintype "passive"))
      (node (ref "C28") (pin "2") (pinfunction "2_2") (pintype "passive"))
      (node (ref "C29") (pin "2") (pinfunction "2_2") (pintype "passive"))
      (node (ref "C3") (pin "2") (pinfunction "2_2") (pintype "passive"))
      (node (ref "C30") (pin "2") (pinfunction "2_2") (pintype "passive"))
      (node (ref "C31") (pin "2") (pinfunction "2_2") (pintype "passive"))
      (node (ref "C32") (pin "2") (pinfunction "2_2") (pintype "passive"))
      (node (ref "C33") (pin "2") (pinfunction "2_2") (pintype "passive"))
      (node (ref "C34") (pin "2") (pinfunction "2_2") (pintype "passive"))
      (node (ref "C35") (pin "2") (pinfunction "2_2") (pintype "passive"))
      (node (ref "C36") (pin "2") (pinfunction "2_2") (pintype "passive"))
      (node (ref "C38") (pin "2") (pinfunction "2_2") (pintype "passive"))
      (node (ref "C39") (pin "2") (pinfunction "2_2") (pintype "passive"))
      (node (ref "C4") (pin "2") (pinfunction "2_2") (pintype "passive"))
      (node (ref "C40") (pin "2") (pinfunction "2_2") (pintype "passive"))
      (node (ref "C41") (pin "2") (pinfunction "2_2") (pintype "passive"))
      (node (ref "C42") (pin "2") (pinfunction "2_2") (pintype "passive"))
      (node (ref "C43") (pin "2") (pinfunction "2_2") (pintype "passive"))
      (node (ref "C44") (pin "2") (pinfunction "2_2") (pintype "passive"))
      (node (ref "C45") (pin "2") (pinfunction "2_2") (pintype "passive"))
      (node (ref "C46") (pin "2") (pinfunction "2_2") (pintype "passive"))
      (node (ref "C47") (pin "2") (pinfunction "2_2") (pintype "passive"))
      (node (ref "C48") (pin "-") (pinfunction "-_-") (pintype "passive"))
      (node (ref "C49") (pin "2") (pinfunction "2_2") (pintype "passive"))
      (node (ref "C5") (pin "2") (pinfunction "2_2") (pintype "passive"))
      (node (ref "C50") (pin "2") (pinfunction "2_2") (pintype "passive"))
      (node (ref "C51") (pin "2") (pinfunction "2_2") (pintype "passive"))
      (node (ref "C52") (pin "2") (pinfunction "2_2") (pintype "passive"))
      (node (ref "C53") (pin "2") (pinfunction "2_2") (pintype "passive"))
      (node (ref "C54") (pin "2") (pinfunction "2_2") (pintype "passive"))
      (node (ref "C55") (pin "2") (pinfunction "2_2") (pintype "passive"))
      (node (ref "C56") (pin "2") (pinfunction "2_2") (pintype "passive"))
      (node (ref "C57") (pin "-") (pinfunction "-_-") (pintype "passive"))
      (node (ref "C58") (pin "2") (pinfunction "2_2") (pintype "passive"))
      (node (ref "C59") (pin "2") (pinfunction "2_2") (pintype "passive"))
      (node (ref "C6") (pin "2") (pinfunction "2_2") (pintype "passive"))
      (node (ref "C60") (pin "2") (pinfunction "2_2") (pintype "passive"))
      (node (ref "C61") (pin "2") (pinfunction "2_2") (pintype "passive"))
      (node (ref "C62") (pin "2") (pinfunction "2_2") (pintype "passive"))
      (node (ref "C7") (pin "2") (pinfunction "2_2") (pintype "passive"))
      (node (ref "C8") (pin "2") (pinfunction "2_2") (pintype "passive"))
      (node (ref "C84") (pin "2") (pinfunction "2_2") (pintype "passive"))
      (node (ref "C85") (pin "2") (pinfunction "2_2") (pintype "passive"))
      (node (ref "C9") (pin "2") (pinfunction "2_2") (pintype "passive"))
      (node (ref "D1") (pin "2") (pinfunction "VSS_2") (pintype "bidirectional"))
      (node (ref "D10") (pin "2") (pinfunction "VSS_2") (pintype "bidirectional"))
      (node (ref "D11") (pin "C") (pinfunction "C_C") (pintype "passive"))
      (node (ref "D12") (pin "C") (pinfunction "C_C") (pintype "passive"))
      (node (ref "D13") (pin "C") (pinfunction "C_C") (pintype "passive"))
      (node (ref "D15") (pin "C") (pinfunction "C_C") (pintype "passive"))
      (node (ref "D16") (pin "C") (pinfunction "C_C") (pintype "passive"))
      (node (ref "D17") (pin "2") (pinfunction "2_2") (pintype "bidirectional"))
      (node (ref "D3") (pin "2") (pinfunction "2_2") (pintype "bidirectional"))
      (node (ref "D7") (pin "2") (pinfunction "VSS_2") (pintype "bidirectional"))
      (node (ref "D8") (pin "2") (pinfunction "VSS_2") (pintype "bidirectional"))
      (node (ref "ESP32_RF") (pin "GND@0") (pinfunction "GND_GND@0") (pintype "bidirectional"))
      (node (ref "ESP32_RF") (pin "GND@1") (pinfunction "GND_GND@1") (pintype "bidirectional"))
      (node (ref "ESP32_RF") (pin "GND@2") (pinfunction "GND_GND@2") (pintype "bidirectional"))
      (node (ref "ESP32_RF") (pin "GND@3") (pinfunction "GND_GND@3") (pintype "bidirectional"))
      (node (ref "GND") (pin "1") (pinfunction "1_1") (pintype "bidirectional"))
      (node (ref "J1") (pin "GND") (pinfunction "GND_GND") (pintype "bidirectional"))
      (node (ref "J1") (pin "GND2") (pinfunction "GND_GND2") (pintype "bidirectional"))
      (node (ref "J13") (pin "1") (pinfunction "1_1") (pintype "passive"))
      (node (ref "J3") (pin "10") (pinfunction "GND_10") (pintype "bidirectional"))
      (node (ref "J3") (pin "11") (pinfunction "GND_11") (pintype "bidirectional"))
      (node (ref "J3") (pin "12") (pinfunction "GND_12") (pintype "bidirectional"))
      (node (ref "J3") (pin "13") (pinfunction "GND_13") (pintype "bidirectional"))
      (node (ref "J3") (pin "6") (pinfunction "GND_6") (pintype "bidirectional"))
      (node (ref "J4") (pin "1") (pinfunction "1_1") (pintype "power_in"))
      (node (ref "J5") (pin "8") (pinfunction "8_8") (pintype "passive"))
      (node (ref "J6") (pin "GND") (pinfunction "GND_GND") (pintype "bidirectional"))
      (node (ref "J6") (pin "GND2") (pinfunction "GND_GND2") (pintype "bidirectional"))
      (node (ref "J8") (pin "1") (pinfunction "GND_1") (pintype "bidirectional"))
      (node (ref "J8") (pin "2") (pinfunction "GND_2") (pintype "bidirectional"))
      (node (ref "LOG_BTN") (pin "1") (pinfunction "1_1") (pintype "passive"))
      (node (ref "MOSAIC_RF") (pin "GND@0") (pinfunction "GND_GND@0") (pintype "bidirectional"))
      (node (ref "MOSAIC_RF") (pin "GND@1") (pinfunction "GND_GND@1") (pintype "bidirectional"))
      (node (ref "MOSAIC_RF") (pin "GND@2") (pinfunction "GND_GND@2") (pintype "bidirectional"))
      (node (ref "MOSAIC_RF") (pin "GND@3") (pinfunction "GND_GND@3") (pintype "bidirectional"))
      (node (ref "R1") (pin "1") (pinfunction "1_1") (pintype "passive"))
      (node (ref "R11") (pin "2") (pinfunction "2_2") (pintype "passive"))
      (node (ref "R13") (pin "2") (pinfunction "2_2") (pintype "passive"))
      (node (ref "R14") (pin "2") (pinfunction "2_2") (pintype "passive"))
      (node (ref "R2") (pin "1") (pinfunction "1_1") (pintype "passive"))
      (node (ref "R24") (pin "2") (pinfunction "2_2") (pintype "passive"))
      (node (ref "R33") (pin "1") (pinfunction "1_1") (pintype "passive"))
      (node (ref "R34") (pin "1") (pinfunction "1_1") (pintype "passive"))
      (node (ref "R43") (pin "1") (pinfunction "1_1") (pintype "passive"))
      (node (ref "R44") (pin "1") (pinfunction "1_1") (pintype "passive"))
      (node (ref "R45") (pin "1") (pinfunction "1_1") (pintype "passive"))
      (node (ref "R48") (pin "2") (pinfunction "2_2") (pintype "passive"))
      (node (ref "R50") (pin "2") (pinfunction "2_2") (pintype "passive"))
      (node (ref "RESET") (pin "1") (pinfunction "1_1") (pintype "passive"))
      (node (ref "SHLD1") (pin "1") (pinfunction "1_1") (pintype "passive"))
      (node (ref "SHLD2") (pin "1") (pinfunction "1_1") (pintype "passive"))
      (node (ref "U1") (pin "1") (pinfunction "GND_1") (pintype "bidirectional"))
      (node (ref "U1") (pin "15") (pinfunction "GND_15") (pintype "bidirectional"))
      (node (ref "U1") (pin "38") (pinfunction "GND_38") (pintype "bidirectional"))
      (node (ref "U1") (pin "GND") (pinfunction "GND_GND") (pintype "bidirectional"))
      (node (ref "U1") (pin "GNDT1") (pinfunction "GND_GNDT1") (pintype "bidirectional"))
      (node (ref "U1") (pin "GNDT2") (pinfunction "GND_GNDT2") (pintype "bidirectional"))
      (node (ref "U1") (pin "GNDT3") (pinfunction "GND_GNDT3") (pintype "bidirectional"))
      (node (ref "U1") (pin "GNDT4") (pinfunction "GND_GNDT4") (pintype "bidirectional"))
      (node (ref "U1") (pin "GNDT5") (pinfunction "GND_GNDT5") (pintype "bidirectional"))
      (node (ref "U1") (pin "GNDT6") (pinfunction "GND_GNDT6") (pintype "bidirectional"))
      (node (ref "U1") (pin "GNDT7") (pinfunction "GND_GNDT7") (pintype "bidirectional"))
      (node (ref "U1") (pin "GNDT8") (pinfunction "GND_GNDT8") (pintype "bidirectional"))
      (node (ref "U10") (pin "3") (pinfunction "VDC-_3") (pintype "bidirectional"))
      (node (ref "U11") (pin "1") (pinfunction "DIR1_1") (pintype "input"))
      (node (ref "U11") (pin "10") (pinfunction "GND_10") (pintype "power_in"))
      (node (ref "U11") (pin "2") (pinfunction "DIR2_2") (pintype "input"))
      (node (ref "U11") (pin "9") (pinfunction "~{OE}_9") (pintype "input"))
      (node (ref "U17") (pin "6") (pinfunction "GND_6") (pintype "power_in"))
      (node (ref "U2") (pin "1") (pinfunction "GND_1") (pintype "bidirectional"))
      (node (ref "U3") (pin "2") (pinfunction "GND_2") (pintype "input"))
      (node (ref "U4") (pin "11") (pinfunction "GND_11") (pintype "bidirectional"))
      (node (ref "U4") (pin "EPAD") (pinfunction "EPAD_EPAD") (pintype "bidirectional"))
      (node (ref "U5") (pin "11") (pinfunction "GND_11") (pintype "bidirectional"))
      (node (ref "U5") (pin "EPAD") (pinfunction "EPAD_EPAD") (pintype "bidirectional"))
      (node (ref "U6") (pin "2") (pinfunction "GND_2") (pintype "input"))
      (node (ref "U7") (pin "1") (pinfunction "GND_1") (pintype "power_in"))
      (node (ref "U7") (pin "GND") (pinfunction "GND_GND") (pintype "power_in"))
      (node (ref "U8") (pin "A15") (pinfunction "GND_A15") (pintype "power_in"))
      (node (ref "U8") (pin "A16") (pinfunction "GND_A16") (pintype "power_in"))
      (node (ref "U8") (pin "A17") (pinfunction "GND_A17") (pintype "power_in"))
      (node (ref "U8") (pin "A21") (pinfunction "GND_A21") (pintype "power_in"))
      (node (ref "U8") (pin "A22") (pinfunction "GND_A22") (pintype "power_in"))
      (node (ref "U8") (pin "A23") (pinfunction "GND_A23") (pintype "power_in"))
      (node (ref "U8") (pin "A3") (pinfunction "RTC_XTALI_A3") (pintype "input"))
      (node (ref "U8") (pin "A4") (pinfunction "GND_A4") (pintype "power_in"))
      (node (ref "U8") (pin "A7") (pinfunction "GND_A7") (pintype "power_in"))
      (node (ref "U8") (pin "AA13") (pinfunction "GND_AA13") (pintype "power_in"))
      (node (ref "U8") (pin "AA14") (pinfunction "GND_AA14") (pintype "power_in"))
      (node (ref "U8") (pin "AA15") (pinfunction "GND_AA15") (pintype "power_in"))
      (node (ref "U8") (pin "AA16") (pinfunction "GND_AA16") (pintype "power_in"))
      (node (ref "U8") (pin "AA17") (pinfunction "GND_AA17") (pintype "power_in"))
      (node (ref "U8") (pin "AA18") (pinfunction "GND_AA18") (pintype "power_in"))
      (node (ref "U8") (pin "AA19") (pinfunction "GND_AA19") (pintype "power_in"))
      (node (ref "U8") (pin "AA20") (pinfunction "GND_AA20") (pintype "power_in"))
      (node (ref "U8") (pin "AA21") (pinfunction "GND_AA21") (pintype "power_in"))
      (node (ref "U8") (pin "AA22") (pinfunction "GND_AA22") (pintype "power_in"))
      (node (ref "U8") (pin "AA23") (pinfunction "GND_AA23") (pintype "power_in"))
      (node (ref "U8") (pin "AB13") (pinfunction "GND_AB13") (pintype "power_in"))
      (node (ref "U8") (pin "AB14") (pinfunction "GND_AB14") (pintype "power_in"))
      (node (ref "U8") (pin "AB15") (pinfunction "GND_AB15") (pintype "power_in"))
      (node (ref "U8") (pin "AB16") (pinfunction "GND_AB16") (pintype "power_in"))
      (node (ref "U8") (pin "AB17") (pinfunction "GND_AB17") (pintype "power_in"))
      (node (ref "U8") (pin "AB18") (pinfunction "GND_AB18") (pintype "power_in"))
      (node (ref "U8") (pin "AB19") (pinfunction "GND_AB19") (pintype "power_in"))
      (node (ref "U8") (pin "AB2") (pinfunction "GND_AB2") (pintype "power_in"))
      (node (ref "U8") (pin "AB20") (pinfunction "GND_AB20") (pintype "power_in"))
      (node (ref "U8") (pin "AB21") (pinfunction "GND_AB21") (pintype "power_in"))
      (node (ref "U8") (pin "AB22") (pinfunction "GND_AB22") (pintype "power_in"))
      (node (ref "U8") (pin "AB23") (pinfunction "GND_AB23") (pintype "power_in"))
      (node (ref "U8") (pin "AB3") (pinfunction "GND_AB3") (pintype "power_in"))
      (node (ref "U8") (pin "AB4") (pinfunction "GND_AB4") (pintype "power_in"))
      (node (ref "U8") (pin "AB5") (pinfunction "GND_AB5") (pintype "power_in"))
      (node (ref "U8") (pin "AB6") (pinfunction "GND_AB6") (pintype "power_in"))
      (node (ref "U8") (pin "AB7") (pinfunction "GND_AB7") (pintype "power_in"))
      (node (ref "U8") (pin "AB8") (pinfunction "GND_AB8") (pintype "power_in"))
      (node (ref "U8") (pin "AC13") (pinfunction "GND_AC13") (pintype "power_in"))
      (node (ref "U8") (pin "AC15") (pinfunction "GND_AC15") (pintype "power_in"))
      (node (ref "U8") (pin "AC18") (pinfunction "GND_AC18") (pintype "power_in"))
      (node (ref "U8") (pin "AC19") (pinfunction "GND_AC19") (pintype "power_in"))
      (node (ref "U8") (pin "AC21") (pinfunction "GND_AC21") (pintype "power_in"))
      (node (ref "U8") (pin "AC22") (pinfunction "GND_AC22") (pintype "power_in"))
      (node (ref "U8") (pin "AC23") (pinfunction "GND_AC23") (pintype "power_in"))
      (node (ref "U8") (pin "B13") (pinfunction "GND_B13") (pintype "power_in"))
      (node (ref "U8") (pin "B17") (pinfunction "GND_B17") (pintype "power_in"))
      (node (ref "U8") (pin "B21") (pinfunction "GND_B21") (pintype "power_in"))
      (node (ref "U8") (pin "B4") (pinfunction "GND_B4") (pintype "power_in"))
      (node (ref "U8") (pin "B5") (pinfunction "GND_B5") (pintype "power_in"))
      (node (ref "U8") (pin "B6") (pinfunction "GND_B6") (pintype "power_in"))
      (node (ref "U8") (pin "B7") (pinfunction "GND_B7") (pintype "power_in"))
      (node (ref "U8") (pin "C15") (pinfunction "GND_C15") (pintype "power_in"))
      (node (ref "U8") (pin "C16") (pinfunction "GND_C16") (pintype "power_in"))
      (node (ref "U8") (pin "C17") (pinfunction "GND_C17") (pintype "power_in"))
      (node (ref "U8") (pin "C23") (pinfunction "GND_C23") (pintype "power_in"))
      (node (ref "U8") (pin "C4") (pinfunction "GND_C4") (pintype "power_in"))
      (node (ref "U8") (pin "C7") (pinfunction "GND_C7") (pintype "power_in"))
      (node (ref "U8") (pin "D2") (pinfunction "GND_D2") (pintype "power_in"))
      (node (ref "U8") (pin "D21") (pinfunction "GND_D21") (pintype "power_in"))
      (node (ref "U8") (pin "D22") (pinfunction "GND_D22") (pintype "power_in"))
      (node (ref "U8") (pin "D23") (pinfunction "GND_D23") (pintype "power_in"))
      (node (ref "U8") (pin "E2") (pinfunction "GND_E2") (pintype "power_in"))
      (node (ref "U8") (pin "E21") (pinfunction "GND_E21") (pintype "power_in"))
      (node (ref "U8") (pin "E22") (pinfunction "GND_E22") (pintype "power_in"))
      (node (ref "U8") (pin "E23") (pinfunction "GND_E23") (pintype "power_in"))
      (node (ref "U8") (pin "F21") (pinfunction "GND_F21") (pintype "power_in"))
      (node (ref "U8") (pin "F22") (pinfunction "GND_F22") (pintype "power_in"))
      (node (ref "U8") (pin "F23") (pinfunction "GND_F23") (pintype "power_in"))
      (node (ref "U8") (pin "G2") (pinfunction "GND_G2") (pintype "power_in"))
      (node (ref "U8") (pin "G21") (pinfunction "GND_G21") (pintype "power_in"))
      (node (ref "U8") (pin "G23") (pinfunction "GND_G23") (pintype "power_in"))
      (node (ref "U8") (pin "H21") (pinfunction "GND_H21") (pintype "power_in"))
      (node (ref "U8") (pin "H22") (pinfunction "GND_H22") (pintype "power_in"))
      (node (ref "U8") (pin "H23") (pinfunction "GND_H23") (pintype "power_in"))
      (node (ref "U8") (pin "J21") (pinfunction "GND_J21") (pintype "power_in"))
      (node (ref "U8") (pin "J22") (pinfunction "GND_J22") (pintype "power_in"))
      (node (ref "U8") (pin "J23") (pinfunction "GND_J23") (pintype "power_in"))
      (node (ref "U8") (pin "K2") (pinfunction "GND_K2") (pintype "power_in"))
      (node (ref "U8") (pin "K21") (pinfunction "GND_K21") (pintype "power_in"))
      (node (ref "U8") (pin "K22") (pinfunction "GND_K22") (pintype "power_in"))
      (node (ref "U8") (pin "K23") (pinfunction "GND_K23") (pintype "power_in"))
      (node (ref "U8") (pin "L21") (pinfunction "GND_L21") (pintype "power_in"))
      (node (ref "U8") (pin "L22") (pinfunction "GND_L22") (pintype "power_in"))
      (node (ref "U8") (pin "L23") (pinfunction "GND_L23") (pintype "power_in"))
      (node (ref "U8") (pin "M21") (pinfunction "GND_M21") (pintype "power_in"))
      (node (ref "U8") (pin "M22") (pinfunction "GND_M22") (pintype "power_in"))
      (node (ref "U8") (pin "N21") (pinfunction "GND_N21") (pintype "power_in"))
      (node (ref "U8") (pin "N22") (pinfunction "GND_N22") (pintype "power_in"))
      (node (ref "U8") (pin "P1") (pinfunction "GND_P1") (pintype "power_in"))
      (node (ref "U8") (pin "P2") (pinfunction "GND_P2") (pintype "power_in"))
      (node (ref "U8") (pin "P21") (pinfunction "GND_P21") (pintype "power_in"))
      (node (ref "U8") (pin "P22") (pinfunction "GND_P22") (pintype "power_in"))
      (node (ref "U8") (pin "P3") (pinfunction "GND_P3") (pintype "power_in"))
      (node (ref "U8") (pin "R21") (pinfunction "GND_R21") (pintype "power_in"))
      (node (ref "U8") (pin "R22") (pinfunction "GND_R22") (pintype "power_in"))
      (node (ref "U8") (pin "R3") (pinfunction "GND_R3") (pintype "power_in"))
      (node (ref "U8") (pin "T21") (pinfunction "GND_T21") (pintype "power_in"))
      (node (ref "U8") (pin "T22") (pinfunction "GND_T22") (pintype "power_in"))
      (node (ref "U8") (pin "T23") (pinfunction "GND_T23") (pintype "power_in"))
      (node (ref "U8") (pin "U2") (pinfunction "GND_U2") (pintype "power_in"))
      (node (ref "U8") (pin "U21") (pinfunction "GND_U21") (pintype "power_in"))
      (node (ref "U8") (pin "U22") (pinfunction "GND_U22") (pintype "power_in"))
      (node (ref "U8") (pin "U23") (pinfunction "GND_U23") (pintype "power_in"))
      (node (ref "U8") (pin "V21") (pinfunction "GND_V21") (pintype "power_in"))
      (node (ref "U8") (pin "V22") (pinfunction "GND_V22") (pintype "power_in"))
      (node (ref "U8") (pin "V23") (pinfunction "ANT_2_V23") (pintype "input"))
      (node (ref "U8") (pin "W21") (pinfunction "GND_W21") (pintype "power_in"))
      (node (ref "U8") (pin "W22") (pinfunction "GND_W22") (pintype "power_in"))
      (node (ref "U8") (pin "W23") (pinfunction "GND_W23") (pintype "power_in"))
      (node (ref "U8") (pin "Y2") (pinfunction "GND_Y2") (pintype "power_in"))
      (node (ref "U8") (pin "Y21") (pinfunction "GND_Y21") (pintype "power_in"))
      (node (ref "U8") (pin "Y22") (pinfunction "GND_Y22") (pintype "power_in"))
      (node (ref "U8") (pin "Y23") (pinfunction "GND_Y23") (pintype "power_in"))
      (node (ref "U9") (pin "1") (pinfunction "GND_1") (pintype "power_in"))
      (node (ref "U9") (pin "GND") (pinfunction "GND_GND") (pintype "power_in"))
    )
    (net (code "55") (name "GND-ISO") (class "Default")
      (node (ref "C25") (pin "1") (pinfunction "1_1") (pintype "passive"))
      (node (ref "C42") (pin "1") (pinfunction "1_1") (pintype "passive"))
      (node (ref "J2") (pin "7") (pinfunction "GND_7") (pintype "bidirectional"))
      (node (ref "J2") (pin "8") (pinfunction "GND_8") (pintype "bidirectional"))
      (node (ref "J2") (pin "S1") (pinfunction "SHLD_S1") (pintype "bidirectional"))
      (node (ref "J2") (pin "S2") (pinfunction "SHLD_S2") (pintype "bidirectional"))
      (node (ref "J9") (pin "7") (pinfunction "GND_7") (pintype "bidirectional"))
      (node (ref "J9") (pin "8") (pinfunction "GND_8") (pintype "bidirectional"))
      (node (ref "J9") (pin "S1") (pinfunction "SHLD_S1") (pintype "bidirectional"))
      (node (ref "J9") (pin "S2") (pinfunction "SHLD_S2") (pintype "bidirectional"))
    )
    (net (code "56") (name "LED_PVT") (class "Default")
      (node (ref "R38") (pin "1") (pinfunction "1_1") (pintype "passive"))
      (node (ref "U8") (pin "A14") (pinfunction "GP_LED_A14") (pintype "output"))
    )
    (net (code "57") (name "LED_RTK") (class "Default")
      (node (ref "R39") (pin "1") (pinfunction "1_1") (pintype "passive"))
      (node (ref "U8") (pin "M3") (pinfunction "GP_LED2_M3") (pintype "output"))
    )
    (net (code "58") (name "LINK_ESP32") (class "Default")
      (node (ref "R25") (pin "2") (pinfunction "2_2") (pintype "passive"))
      (node (ref "U7") (pin "30") (pinfunction "LED0/NWAYEN_30") (pintype "output"))
    )
    (net (code "59") (name "LINK_MOSAIC") (class "Default")
      (node (ref "R6") (pin "2") (pinfunction "2_2") (pintype "passive"))
      (node (ref "U9") (pin "30") (pinfunction "LED0/NWAYEN_30") (pintype "output"))
    )
    (net (code "60") (name "LOG_LED") (class "Default")
      (node (ref "R37") (pin "1") (pinfunction "1_1") (pintype "passive"))
      (node (ref "U8") (pin "B2") (pinfunction "LOG_LED_B2") (pintype "output"))
    )
    (net (code "61") (name "MOSAIC_CTS") (class "Default")
      (node (ref "U4") (pin "5") (pinfunction "A4_5") (pintype "bidirectional"))
      (node (ref "U8") (pin "E1") (pinfunction "COM1_CTS_E1") (pintype "input"))
    )
    (net (code "62") (name "MOSAIC_CTS_IO") (class "Default")
      (node (ref "J5") (pin "3") (pinfunction "3_3") (pintype "passive"))
      (node (ref "U4") (pin "16") (pinfunction "B4_16") (pintype "bidirectional"))
    )
    (net (code "63") (name "MOSAIC_EVENTA") (class "Default")
      (node (ref "U11") (pin "14") (pinfunction "B1_14") (pintype "bidirectional"))
      (node (ref "U4") (pin "6") (pinfunction "A5_6") (pintype "bidirectional"))
    )
    (net (code "64") (name "MOSAIC_EVENTA_1V8") (class "Default")
      (node (ref "U11") (pin "3") (pinfunction "A1_3") (pintype "bidirectional"))
      (node (ref "U8") (pin "AC6") (pinfunction "EVENTA_AC6") (pintype "input"))
    )
    (net (code "65") (name "MOSAIC_EVENTA_IO") (class "Default")
      (node (ref "J5") (pin "2") (pinfunction "2_2") (pintype "passive"))
      (node (ref "R43") (pin "2") (pinfunction "2_2") (pintype "passive"))
      (node (ref "U4") (pin "15") (pinfunction "B5_15") (pintype "bidirectional"))
    )
    (net (code "66") (name "MOSAIC_EVENTB") (class "Default")
      (node (ref "U11") (pin "13") (pinfunction "B2_13") (pintype "bidirectional"))
      (node (ref "U4") (pin "7") (pinfunction "A6_7") (pintype "bidirectional"))
    )
    (net (code "67") (name "MOSAIC_EVENTB_1V8") (class "Default")
      (node (ref "U11") (pin "4") (pinfunction "A2_4") (pintype "bidirectional"))
      (node (ref "U8") (pin "AC7") (pinfunction "EVENTB_AC7") (pintype "input"))
    )
    (net (code "68") (name "MOSAIC_EVENTB_IO") (class "Default")
      (node (ref "J5") (pin "1") (pinfunction "1_1") (pintype "passive"))
      (node (ref "R44") (pin "2") (pinfunction "2_2") (pintype "passive"))
      (node (ref "U4") (pin "14") (pinfunction "B6_14") (pintype "bidirectional"))
    )
    (net (code "69") (name "MOSAIC_LOG_BTN") (class "Default")
      (node (ref "U4") (pin "9") (pinfunction "A8_9") (pintype "bidirectional"))
      (node (ref "U8") (pin "K3") (pinfunction "LOG_BTN_K3") (pintype "input"))
    )
    (net (code "70") (name "MOSAIC_LOG_BTN_IO") (class "Default")
      (node (ref "J13") (pin "9") (pinfunction "9_9") (pintype "passive"))
      (node (ref "R23") (pin "2") (pinfunction "2_2") (pintype "passive"))
      (node (ref "R27") (pin "2") (pinfunction "2_2") (pintype "passive"))
      (node (ref "U4") (pin "12") (pinfunction "B8_12") (pintype "bidirectional"))
    )
    (net (code "71") (name "MOSAIC_PPSO") (class "Default")
      (node (ref "U11") (pin "12") (pinfunction "B3_12") (pintype "bidirectional"))
      (node (ref "U4") (pin "8") (pinfunction "A7_8") (pintype "bidirectional"))
    )
    (net (code "72") (name "MOSAIC_PPSO_1V8") (class "Default")
      (node (ref "U11") (pin "5") (pinfunction "A3_5") (pintype "bidirectional"))
      (node (ref "U8") (pin "AC8") (pinfunction "PPS_AC8") (pintype "output"))
    )
    (net (code "73") (name "MOSAIC_PPSO_IO") (class "Default")
      (node (ref "J13") (pin "10") (pinfunction "10_10") (pintype "passive"))
      (node (ref "U4") (pin "13") (pinfunction "B7_13") (pintype "bidirectional"))
    )
    (net (code "74") (name "MOSAIC_RF") (class "Default")
      (node (ref "D17") (pin "1") (pinfunction "1_1") (pintype "bidirectional"))
      (node (ref "MOSAIC_RF") (pin "SIG") (pinfunction "SIGNAL_SIG") (pintype "bidirectional"))
      (node (ref "U8") (pin "AC20") (pinfunction "ANT_1_AC20") (pintype "input"))
    )
    (net (code "75") (name "MOSAIC_RTS") (class "Default")
      (node (ref "U4") (pin "4") (pinfunction "A3_4") (pintype "bidirectional"))
      (node (ref "U8") (pin "C1") (pinfunction "COM1_RTS_C1") (pintype "output"))
    )
    (net (code "76") (name "MOSAIC_RTS_IO") (class "Default")
      (node (ref "J5") (pin "4") (pinfunction "4_4") (pintype "passive"))
      (node (ref "U4") (pin "17") (pinfunction "B3_17") (pintype "bidirectional"))
    )
    (net (code "77") (name "MOSAIC_RX") (class "Default")
      (node (ref "U4") (pin "1") (pinfunction "A1_1") (pintype "bidirectional"))
      (node (ref "U8") (pin "B1") (pinfunction "COM1_RX_B1") (pintype "input"))
    )
    (net (code "78") (name "MOSAIC_RX_IO") (class "Default")
      (node (ref "J5") (pin "6") (pinfunction "6_6") (pintype "passive"))
      (node (ref "U4") (pin "20") (pinfunction "B1_20") (pintype "bidirectional"))
    )
    (net (code "79") (name "MOSAIC_TX") (class "Default")
      (node (ref "U4") (pin "3") (pinfunction "A2_3") (pintype "bidirectional"))
      (node (ref "U8") (pin "D1") (pinfunction "COM1_TX_D1") (pintype "output"))
    )
    (net (code "80") (name "MOSAIC_TX_IO") (class "Default")
      (node (ref "J5") (pin "5") (pinfunction "5_5") (pintype "passive"))
      (node (ref "U4") (pin "18") (pinfunction "B2_18") (pintype "bidirectional"))
    )
    (net (code "81") (name "MOSAIC_~{RST}") (class "Default")
      (node (ref "MOSAIC_RST") (pin "1") (pinfunction "1_1") (pintype "passive"))
      (node (ref "MOSAIC_RST") (pin "3") (pinfunction "1_3") (pintype "passive"))
      (node (ref "U8") (pin "A11") (pinfunction "~{RST}_A11") (pintype "input"))
    )
    (net (code "82") (name "Net-(ACT-Pad2)") (class "Default")
      (node (ref "ACT") (pin "2") (pinfunction "2_2") (pintype "passive"))
      (node (ref "R26") (pin "1") (pinfunction "1_1") (pintype "passive"))
    )
    (net (code "83") (name "Net-(ACT2-Pad2)") (class "Default")
      (node (ref "ACT2") (pin "2") (pinfunction "2_2") (pintype "passive"))
      (node (ref "R7") (pin "1") (pinfunction "1_1") (pintype "passive"))
    )
    (net (code "84") (name "Net-(BOOT-Pad2)") (class "Default")
      (node (ref "BOOT") (pin "2") (pinfunction "2_2") (pintype "passive"))
      (node (ref "BOOT_SW") (pin "2") (pinfunction "2_2") (pintype "passive"))
    )
    (net (code "85") (name "Net-(BT-Pad1)") (class "Default")
      (node (ref "BT") (pin "1") (pinfunction "1_1") (pintype "passive"))
      (node (ref "D12") (pin "A") (pinfunction "A_A") (pintype "passive"))
    )
    (net (code "86") (name "Net-(BT-Pad2)") (class "Default")
      (node (ref "BT") (pin "2") (pinfunction "2_2") (pintype "passive"))
      (node (ref "R36") (pin "2") (pinfunction "2_2") (pintype "passive"))
    )
    (net (code "87") (name "Net-(C27-Pad1)") (class "Default")
      (node (ref "C27") (pin "1") (pinfunction "1_1") (pintype "passive"))
      (node (ref "R35") (pin "2") (pinfunction "2_2") (pintype "passive"))
      (node (ref "R40") (pin "2") (pinfunction "2_2") (pintype "passive"))
    )
    (net (code "88") (name "Net-(C28-Pad1)") (class "Default")
      (node (ref "C28") (pin "1") (pinfunction "1_1") (pintype "passive"))
      (node (ref "R41") (pin "2") (pinfunction "2_2") (pintype "passive"))
      (node (ref "R42") (pin "2") (pinfunction "2_2") (pintype "passive"))
    )
    (net (code "89") (name "Net-(C29-Pad1)") (class "Default")
      (node (ref "C29") (pin "1") (pinfunction "1_1") (pintype "passive"))
      (node (ref "R8") (pin "2") (pinfunction "2_2") (pintype "passive"))
      (node (ref "R9") (pin "2") (pinfunction "2_2") (pintype "passive"))
    )
    (net (code "90") (name "Net-(C30-Pad1)") (class "Default")
      (node (ref "C30") (pin "1") (pinfunction "1_1") (pintype "passive"))
      (node (ref "R10") (pin "2") (pinfunction "2_2") (pintype "passive"))
      (node (ref "R12") (pin "2") (pinfunction "2_2") (pintype "passive"))
    )
    (net (code "91") (name "Net-(C48-Pad+)") (class "Default")
      (node (ref "C48") (pin "+") (pinfunction "+_+") (pintype "passive"))
      (node (ref "C49") (pin "1") (pinfunction "1_1") (pintype "passive"))
      (node (ref "C50") (pin "1") (pinfunction "1_1") (pintype "passive"))
      (node (ref "L1") (pin "1") (pinfunction "1_1") (pintype "passive"))
      (node (ref "U10") (pin "1") (pinfunction "VDC+_1") (pintype "bidirectional"))
      (node (ref "U10") (pin "2") (pinfunction "VDC+_2") (pintype "bidirectional"))
    )
    (net (code "92") (name "Net-(D4-PadC)") (class "Default")
      (node (ref "D4") (pin "C") (pinfunction "C_C") (pintype "passive"))
      (node (ref "D5") (pin "C") (pinfunction "C_C") (pintype "passive"))
      (node (ref "D6") (pin "C") (pinfunction "C_C") (pintype "passive"))
      (node (ref "D9") (pin "C") (pinfunction "C_C") (pintype "passive"))
      (node (ref "MEAS") (pin "2") (pinfunction "2_2") (pintype "passive"))
      (node (ref "MEAS") (pin "4") (pinfunction "2_4") (pintype "passive"))
    )
    (net (code "93") (name "Net-(D11-PadA)") (class "Default")
      (node (ref "D11") (pin "A") (pinfunction "A_A") (pintype "passive"))
      (node (ref "WIFI") (pin "1") (pinfunction "1_1") (pintype "passive"))
    )
    (net (code "94") (name "Net-(D13-PadA)") (class "Default")
      (node (ref "D13") (pin "A") (pinfunction "A_A") (pintype "passive"))
      (node (ref "LOG") (pin "1") (pinfunction "1_1") (pintype "passive"))
    )
    (net (code "95") (name "Net-(D14-PadA)") (class "Default")
      (node (ref "D14") (pin "A") (pinfunction "A_A") (pintype "passive"))
      (node (ref "VIN+") (pin "1") (pinfunction "1_1") (pintype "passive"))
      (node (ref "VIN+") (pin "3") (pinfunction "1_3") (pintype "passive"))
    )
    (net (code "96") (name "Net-(D15-PadA)") (class "Default")
      (node (ref "D15") (pin "A") (pinfunction "A_A") (pintype "passive"))
      (node (ref "PVT") (pin "1") (pinfunction "1_1") (pintype "passive"))
    )
    (net (code "97") (name "Net-(D16-PadA)") (class "Default")
      (node (ref "D16") (pin "A") (pinfunction "A_A") (pintype "passive"))
      (node (ref "RTK") (pin "1") (pinfunction "1_1") (pintype "passive"))
    )
    (net (code "98") (name "Net-(ESP32_RF-SIGNAL)") (class "Default")
      (node (ref "D3") (pin "1") (pinfunction "1_1") (pintype "bidirectional"))
      (node (ref "ESP32_RF") (pin "SIG") (pinfunction "SIGNAL_SIG") (pintype "bidirectional"))
      (node (ref "J8") (pin "FEED") (pinfunction "SIGNAL_FEED") (pintype "bidirectional"))
    )
    (net (code "99") (name "Net-(F1-Pad2)") (class "Default")
      (node (ref "F1") (pin "2") (pinfunction "2_2") (pintype "bidirectional"))
      (node (ref "MEAS") (pin "1") (pinfunction "1_1") (pintype "passive"))
      (node (ref "MEAS") (pin "3") (pinfunction "1_3") (pintype "passive"))
    )
    (net (code "100") (name "Net-(FB3-Pad2)") (class "Default")
      (node (ref "FB3") (pin "2") (pinfunction "2_2") (pintype "passive"))
      (node (ref "U8") (pin "P23") (pinfunction "VANT_P23") (pintype "input"))
      (node (ref "U8") (pin "R23") (pinfunction "VANT_R23") (pintype "input"))
    )
    (net (code "101") (name "Net-(I2C-Pad1)") (class "Default")
      (node (ref "I2C") (pin "1") (pinfunction "1_1") (pintype "passive"))
      (node (ref "R_SDA") (pin "2") (pinfunction "2_2") (pintype "passive"))
    )
    (net (code "102") (name "Net-(I2C-Pad3)") (class "Default")
      (node (ref "I2C") (pin "3") (pinfunction "3_3") (pintype "passive"))
      (node (ref "R_SCL") (pin "2") (pinfunction "2_2") (pintype "passive"))
    )
    (net (code "103") (name "Net-(J1-CC1)") (class "Default")
      (node (ref "J1") (pin "A5") (pinfunction "CC1_A5") (pintype "bidirectional"))
      (node (ref "R2") (pin "2") (pinfunction "2_2") (pintype "passive"))
    )
    (net (code "104") (name "Net-(J1-CC2)") (class "Default")
      (node (ref "J1") (pin "B5") (pinfunction "CC2_B5") (pintype "bidirectional"))
      (node (ref "R1") (pin "2") (pinfunction "2_2") (pintype "passive"))
    )
    (net (code "105") (name "Net-(J1-SHLD-PadSHLD1)") (class "Default")
      (node (ref "J1") (pin "SHLD1") (pinfunction "SHLD_SHLD1") (pintype "bidirectional"))
      (node (ref "J1") (pin "SHLD2") (pinfunction "SHLD_SHLD2") (pintype "bidirectional"))
      (node (ref "J1") (pin "SHLD3") (pinfunction "SHLD_SHLD3") (pintype "bidirectional"))
      (node (ref "J1") (pin "SHLD4") (pinfunction "SHLD_SHLD4") (pintype "bidirectional"))
      (node (ref "SHLD1") (pin "2") (pinfunction "2_2") (pintype "passive"))
    )
    (net (code "106") (name "Net-(J2-GRN-)") (class "Default")
      (node (ref "ACT2") (pin "1") (pinfunction "1_1") (pintype "passive"))
      (node (ref "J2") (pin "14") (pinfunction "GRN-_14") (pintype "bidirectional"))
    )
    (net (code "107") (name "Net-(J2-YLW-)") (class "Default")
      (node (ref "J2") (pin "12") (pinfunction "YLW-_12") (pintype "bidirectional"))
      (node (ref "LINK2") (pin "1") (pinfunction "1_1") (pintype "passive"))
    )
    (net (code "108") (name "Net-(J3-DAT3{slash}~{CS})") (class "Default")
      (node (ref "J3") (pin "2") (pinfunction "DAT3/~{CS}_2") (pintype "bidirectional"))
      (node (ref "R17") (pin "1") (pinfunction "1_1") (pintype "passive"))
    )
    (net (code "109") (name "Net-(J6-CC1)") (class "Default")
      (node (ref "J6") (pin "A5") (pinfunction "CC1_A5") (pintype "bidirectional"))
      (node (ref "R34") (pin "2") (pinfunction "2_2") (pintype "passive"))
    )
    (net (code "110") (name "Net-(J6-CC2)") (class "Default")
      (node (ref "J6") (pin "B5") (pinfunction "CC2_B5") (pintype "bidirectional"))
      (node (ref "R33") (pin "2") (pinfunction "2_2") (pintype "passive"))
    )
    (net (code "111") (name "Net-(J6-SHLD-PadSHLD1)") (class "Default")
      (node (ref "J6") (pin "SHLD1") (pinfunction "SHLD_SHLD1") (pintype "bidirectional"))
      (node (ref "J6") (pin "SHLD2") (pinfunction "SHLD_SHLD2") (pintype "bidirectional"))
      (node (ref "J6") (pin "SHLD3") (pinfunction "SHLD_SHLD3") (pintype "bidirectional"))
      (node (ref "J6") (pin "SHLD4") (pinfunction "SHLD_SHLD4") (pintype "bidirectional"))
      (node (ref "SHLD2") (pin "2") (pinfunction "2_2") (pintype "passive"))
    )
    (net (code "112") (name "Net-(J9-GRN-)") (class "Default")
      (node (ref "ACT") (pin "1") (pinfunction "1_1") (pintype "passive"))
      (node (ref "J9") (pin "14") (pinfunction "GRN-_14") (pintype "bidirectional"))
    )
    (net (code "113") (name "Net-(J9-YLW-)") (class "Default")
      (node (ref "J9") (pin "12") (pinfunction "YLW-_12") (pintype "bidirectional"))
      (node (ref "LINK") (pin "1") (pinfunction "1_1") (pintype "passive"))
    )
    (net (code "114") (name "Net-(LINK-Pad2)") (class "Default")
      (node (ref "LINK") (pin "2") (pinfunction "2_2") (pintype "passive"))
      (node (ref "R25") (pin "1") (pinfunction "1_1") (pintype "passive"))
    )
    (net (code "115") (name "Net-(LINK2-Pad2)") (class "Default")
      (node (ref "LINK2") (pin "2") (pinfunction "2_2") (pintype "passive"))
      (node (ref "R6") (pin "1") (pinfunction "1_1") (pintype "passive"))
    )
    (net (code "116") (name "Net-(LOAD-Pad1)") (class "Default")
      (node (ref "LOAD") (pin "1") (pinfunction "1_1") (pintype "passive"))
      (node (ref "R45") (pin "2") (pinfunction "2_2") (pintype "passive"))
    )
    (net (code "117") (name "Net-(LOG-Pad2)") (class "Default")
      (node (ref "LOG") (pin "2") (pinfunction "2_2") (pintype "passive"))
      (node (ref "R37") (pin "2") (pinfunction "2_2") (pintype "passive"))
    )
    (net (code "118") (name "Net-(LOG_BTN-Pad2)") (class "Default")
      (node (ref "LOG_BTN") (pin "2") (pinfunction "2_2") (pintype "passive"))
      (node (ref "R27") (pin "1") (pinfunction "1_1") (pintype "passive"))
    )
    (net (code "119") (name "Net-(PVT-Pad2)") (class "Default")
      (node (ref "PVT") (pin "2") (pinfunction "2_2") (pintype "passive"))
      (node (ref "R38") (pin "2") (pinfunction "2_2") (pintype "passive"))
    )
    (net (code "120") (name "Net-(PW+-1-Pad3)") (class "Default")
      (node (ref "PW+") (pin "1") (pinfunction "1_1") (pintype "passive"))
      (node (ref "PW+") (pin "3") (pinfunction "1_3") (pintype "passive"))
      (node (ref "U10") (pin "5") (pinfunction "VIN+_5") (pintype "bidirectional"))
      (node (ref "U10") (pin "6") (pinfunction "VIN+_6") (pintype "bidirectional"))
    )
    (net (code "121") (name "Net-(PW--1-Pad3)") (class "Default")
      (node (ref "PW-") (pin "1") (pinfunction "1_1") (pintype "passive"))
      (node (ref "PW-") (pin "3") (pinfunction "1_3") (pintype "passive"))
      (node (ref "U10") (pin "7") (pinfunction "VIN-_7") (pintype "bidirectional"))
      (node (ref "U10") (pin "8") (pinfunction "VIN-_8") (pintype "bidirectional"))
    )
    (net (code "122") (name "Net-(Q1A-B)") (class "Default")
      (node (ref "Q1") (pin "5") (pinfunction "B_5") (pintype "passive"))
      (node (ref "R4") (pin "1") (pinfunction "1_1") (pintype "passive"))
    )
    (net (code "123") (name "Net-(Q1B-B)") (class "Default")
      (node (ref "Q1") (pin "2") (pinfunction "B_2") (pintype "passive"))
      (node (ref "R5") (pin "1") (pinfunction "1_1") (pintype "passive"))
    )
    (net (code "124") (name "Net-(R28-Pad2)") (class "Default")
      (node (ref "R28") (pin "2") (pinfunction "2_2") (pintype "passive"))
      (node (ref "WIFI") (pin "2") (pinfunction "2_2") (pintype "passive"))
    )
    (net (code "125") (name "Net-(R39-Pad2)") (class "Default")
      (node (ref "R39") (pin "2") (pinfunction "2_2") (pintype "passive"))
      (node (ref "RTK") (pin "2") (pinfunction "2_2") (pintype "passive"))
    )
    (net (code "126") (name "Net-(RESET-Pad2)") (class "Default")
      (node (ref "RESET") (pin "2") (pinfunction "2_2") (pintype "passive"))
      (node (ref "RESET_SW") (pin "2") (pinfunction "2_2") (pintype "passive"))
    )
    (net (code "127") (name "Net-(U7-COL{slash}CONFIG0)") (class "Default")
      (node (ref "R29") (pin "1") (pinfunction "1_1") (pintype "passive"))
      (node (ref "U7") (pin "28") (pinfunction "COL/CONFIG0_28") (pintype "bidirectional"))
    )
    (net (code "128") (name "Net-(U7-REXT)") (class "Default")
      (node (ref "C34") (pin "1") (pinfunction "1_1") (pintype "passive"))
      (node (ref "R11") (pin "1") (pinfunction "1_1") (pintype "passive"))
      (node (ref "R24") (pin "1") (pinfunction "1_1") (pintype "passive"))
      (node (ref "U7") (pin "10") (pinfunction "REXT_10") (pintype "bidirectional"))
    )
    (net (code "129") (name "Net-(U7-RXD0{slash}DUPLEX)") (class "Default")
      (node (ref "R30") (pin "2") (pinfunction "2_2") (pintype "passive"))
      (node (ref "U7") (pin "16") (pinfunction "RXD0/DUPLEX_16") (pintype "bidirectional"))
    )
    (net (code "130") (name "Net-(U7-RXD1{slash}PHYAD2)") (class "Default")
      (node (ref "R31") (pin "2") (pinfunction "2_2") (pintype "passive"))
      (node (ref "U7") (pin "15") (pinfunction "RXD1/PHYAD2_15") (pintype "bidirectional"))
    )
    (net (code "131") (name "Net-(U7-RXDV{slash}CONFIG2)") (class "Default")
      (node (ref "R32") (pin "2") (pinfunction "2_2") (pintype "passive"))
      (node (ref "U7") (pin "18") (pinfunction "RXDV/CONFIG2_18") (pintype "bidirectional"))
    )
    (net (code "132") (name "Net-(U7-VDDP)") (class "Default")
      (node (ref "C23") (pin "1") (pinfunction "1_1") (pintype "passive"))
      (node (ref "C33") (pin "1") (pinfunction "1_1") (pintype "passive"))
      (node (ref "U7") (pin "2") (pinfunction "VDDP_2") (pintype "bidirectional"))
    )
    (net (code "133") (name "Net-(U8-2V8_IN)") (class "Default")
      (node (ref "2V8") (pin "1") (pinfunction "1_1") (pintype "bidirectional"))
      (node (ref "U8") (pin "M23") (pinfunction "2V8_IN_M23") (pintype "input"))
      (node (ref "U8") (pin "N23") (pinfunction "2V8_OUT_N23") (pintype "output"))
    )
    (net (code "134") (name "Net-(U8-COM2_CTS)") (class "Default")
      (node (ref "COM2_CTS") (pin "1") (pinfunction "1_1") (pintype "bidirectional"))
      (node (ref "U8") (pin "J1") (pinfunction "COM2_CTS_J1") (pintype "input"))
    )
    (net (code "135") (name "Net-(U8-COM2_RTS)") (class "Default")
      (node (ref "COM2_RTS") (pin "1") (pinfunction "1_1") (pintype "bidirectional"))
      (node (ref "U8") (pin "G1") (pinfunction "COM2_RTS_G1") (pintype "output"))
    )
    (net (code "136") (name "Net-(U8-COM2_RX)") (class "Default")
      (node (ref "COM2_RX") (pin "1") (pinfunction "1_1") (pintype "bidirectional"))
      (node (ref "U8") (pin "F1") (pinfunction "COM2_RX_F1") (pintype "input"))
    )
    (net (code "137") (name "Net-(U8-COM2_TX)") (class "Default")
      (node (ref "COM2_TX") (pin "1") (pinfunction "1_1") (pintype "bidirectional"))
      (node (ref "U8") (pin "H1") (pinfunction "COM2_TX_H1") (pintype "output"))
    )
    (net (code "138") (name "Net-(U8-COM3_CTS)") (class "Default")
      (node (ref "COM3_CTS") (pin "1") (pinfunction "1_1") (pintype "bidirectional"))
      (node (ref "U8") (pin "N1") (pinfunction "COM3_CTS_N1") (pintype "input"))
    )
    (net (code "139") (name "Net-(U8-COM3_RTS)") (class "Default")
      (node (ref "COM3_RTS") (pin "1") (pinfunction "1_1") (pintype "bidirectional"))
      (node (ref "U8") (pin "L1") (pinfunction "COM3_RTS_L1") (pintype "output"))
    )
    (net (code "140") (name "Net-(U8-COM3_RX)") (class "Default")
      (node (ref "COM3_RX") (pin "1") (pinfunction "1_1") (pintype "bidirectional"))
      (node (ref "U8") (pin "K1") (pinfunction "COM3_RX_K1") (pintype "input"))
    )
    (net (code "141") (name "Net-(U8-COM3_TX)") (class "Default")
      (node (ref "COM3_TX") (pin "1") (pinfunction "1_1") (pintype "bidirectional"))
      (node (ref "U8") (pin "M1") (pinfunction "COM3_TX_M1") (pintype "output"))
    )
    (net (code "142") (name "Net-(U8-GPIO_1)") (class "Default")
      (node (ref "GPIO_1") (pin "1") (pinfunction "1_1") (pintype "bidirectional"))
      (node (ref "U8") (pin "AA4") (pinfunction "GPIO_1_AA4") (pintype "output"))
    )
    (net (code "143") (name "Net-(U8-GPIO_2)") (class "Default")
      (node (ref "GPIO_2") (pin "1") (pinfunction "1_1") (pintype "bidirectional"))
      (node (ref "U8") (pin "L3") (pinfunction "GPIO_2_L3") (pintype "output"))
    )
    (net (code "144") (name "Net-(U8-MODULE_RDY)") (class "Default")
      (node (ref "RDY") (pin "1") (pinfunction "1_1") (pintype "bidirectional"))
      (node (ref "U8") (pin "A12") (pinfunction "MODULE_RDY_A12") (pintype "output"))
    )
    (net (code "145") (name "Net-(U8-REF_IN)") (class "Default")
      (node (ref "REF") (pin "1") (pinfunction "1_1") (pintype "bidirectional"))
      (node (ref "U8") (pin "AC16") (pinfunction "REF_OUT_AC16") (pintype "output"))
      (node (ref "U8") (pin "AC17") (pinfunction "REF_IN_AC17") (pintype "input"))
    )
    (net (code "146") (name "Net-(U8-SYNC)") (class "Default")
      (node (ref "R18") (pin "1") (pinfunction "1_1") (pintype "passive"))
      (node (ref "U8") (pin "AC3") (pinfunction "SYNC_AC3") (pintype "input"))
    )
    (net (code "147") (name "Net-(U9-COL{slash}CONFIG0)") (class "Default")
      (node (ref "R15") (pin "1") (pinfunction "1_1") (pintype "passive"))
      (node (ref "U9") (pin "28") (pinfunction "COL/CONFIG0_28") (pintype "bidirectional"))
    )
    (net (code "148") (name "Net-(U9-REXT)") (class "Default")
      (node (ref "C40") (pin "1") (pinfunction "1_1") (pintype "passive"))
      (node (ref "R13") (pin "1") (pinfunction "1_1") (pintype "passive"))
      (node (ref "R14") (pin "1") (pinfunction "1_1") (pintype "passive"))
      (node (ref "U9") (pin "10") (pinfunction "REXT_10") (pintype "bidirectional"))
    )
    (net (code "149") (name "Net-(U9-VDDP)") (class "Default")
      (node (ref "C35") (pin "1") (pinfunction "1_1") (pintype "passive"))
      (node (ref "C36") (pin "1") (pinfunction "1_1") (pintype "passive"))
      (node (ref "U9") (pin "2") (pinfunction "VDDP_2") (pintype "bidirectional"))
    )
    (net (code "150") (name "Net-(U17-VIN+)") (class "Default")
      (node (ref "C86") (pin "+") (pinfunction "+_+") (pintype "passive"))
      (node (ref "D14") (pin "C") (pinfunction "C_C") (pintype "passive"))
      (node (ref "U17") (pin "3") (pinfunction "VIN+_3") (pintype "power_in"))
    )
    (net (code "151") (name "Net-(U17-VIN-)") (class "Default")
      (node (ref "C86") (pin "-") (pinfunction "-_-") (pintype "passive"))
      (node (ref "U17") (pin "2") (pinfunction "VIN-_2") (pintype "power_in"))
      (node (ref "VIN-") (pin "2") (pinfunction "2_2") (pintype "passive"))
      (node (ref "VIN-") (pin "4") (pinfunction "2_4") (pintype "passive"))
    )
    (net (code "152") (name "Net-(U17-VOUT)") (class "Default")
      (node (ref "C16") (pin "+") (pinfunction "+_+") (pintype "passive"))
      (node (ref "C51") (pin "1") (pinfunction "1_1") (pintype "passive"))
      (node (ref "C84") (pin "1") (pinfunction "1_1") (pintype "passive"))
      (node (ref "L4") (pin "1") (pinfunction "1_1") (pintype "passive"))
      (node (ref "U17") (pin "4") (pinfunction "VOUT_4") (pintype "power_in"))
    )
    (net (code "153") (name "PW+") (class "Default")
      (node (ref "J2") (pin "9") (pinfunction "PW+_9") (pintype "bidirectional"))
      (node (ref "PW+") (pin "2") (pinfunction "2_2") (pintype "passive"))
      (node (ref "PW+") (pin "4") (pinfunction "2_4") (pintype "passive"))
    )
    (net (code "154") (name "PW-") (class "Default")
      (node (ref "J2") (pin "10") (pinfunction "PW-_10") (pintype "bidirectional"))
      (node (ref "PW-") (pin "2") (pinfunction "2_2") (pintype "passive"))
      (node (ref "PW-") (pin "4") (pinfunction "2_4") (pintype "passive"))
    )
    (net (code "155") (name "RD+_ESP32") (class "Default")
      (node (ref "D7") (pin "4") (pinfunction "IO3_4") (pintype "bidirectional"))
      (node (ref "J9") (pin "3") (pinfunction "RD+_3") (pintype "bidirectional"))
      (node (ref "R42") (pin "1") (pinfunction "1_1") (pintype "passive"))
      (node (ref "U7") (pin "5") (pinfunction "RX+_5") (pintype "bidirectional"))
    )
    (net (code "156") (name "RD+_MOSAIC") (class "Default")
      (node (ref "D1") (pin "1") (pinfunction "IO1_1") (pintype "bidirectional"))
      (node (ref "J2") (pin "3") (pinfunction "RD+_3") (pintype "bidirectional"))
      (node (ref "R12") (pin "1") (pinfunction "1_1") (pintype "passive"))
      (node (ref "U9") (pin "5") (pinfunction "RX+_5") (pintype "bidirectional"))
    )
    (net (code "157") (name "RD-_ESP32") (class "Default")
      (node (ref "D7") (pin "6") (pinfunction "IO4_6") (pintype "bidirectional"))
      (node (ref "J9") (pin "6") (pinfunction "RD-_6") (pintype "bidirectional"))
      (node (ref "R41") (pin "1") (pinfunction "1_1") (pintype "passive"))
      (node (ref "U7") (pin "4") (pinfunction "RX-_4") (pintype "bidirectional"))
    )
    (net (code "158") (name "RD-_MOSAIC") (class "Default")
      (node (ref "D1") (pin "3") (pinfunction "IO2_3") (pintype "bidirectional"))
      (node (ref "J2") (pin "6") (pinfunction "RD-_6") (pintype "bidirectional"))
      (node (ref "R10") (pin "1") (pinfunction "1_1") (pintype "passive"))
      (node (ref "U9") (pin "4") (pinfunction "RX-_4") (pintype "bidirectional"))
    )
    (net (code "159") (name "SD_CLK") (class "Default")
      (node (ref "J3") (pin "5") (pinfunction "CLK/SCK_5") (pintype "bidirectional"))
      (node (ref "U8") (pin "AA1") (pinfunction "SD_CLK_AA1") (pintype "output"))
    )
    (net (code "160") (name "SD_CMD") (class "Default")
      (node (ref "J3") (pin "3") (pinfunction "CMD/SDI_3") (pintype "bidirectional"))
      (node (ref "R46") (pin "1") (pinfunction "1_1") (pintype "passive"))
      (node (ref "U8") (pin "AB1") (pinfunction "SD_CMD_AB1") (pintype "output"))
    )
    (net (code "161") (name "SD_DATA") (class "Default")
      (node (ref "J3") (pin "7") (pinfunction "DAT0/SDO_7") (pintype "bidirectional"))
      (node (ref "R47") (pin "1") (pinfunction "1_1") (pintype "passive"))
      (node (ref "U8") (pin "Y1") (pinfunction "SD_DATA_Y1") (pintype "bidirectional"))
    )
    (net (code "162") (name "TD+_ESP32") (class "Default")
      (node (ref "D7") (pin "3") (pinfunction "IO2_3") (pintype "bidirectional"))
      (node (ref "J9") (pin "1") (pinfunction "TD+_1") (pintype "bidirectional"))
      (node (ref "R35") (pin "1") (pinfunction "1_1") (pintype "passive"))
      (node (ref "U7") (pin "7") (pinfunction "TX+_7") (pintype "bidirectional"))
    )
    (net (code "163") (name "TD+_MOSAIC") (class "Default")
      (node (ref "D1") (pin "6") (pinfunction "IO4_6") (pintype "bidirectional"))
      (node (ref "J2") (pin "1") (pinfunction "TD+_1") (pintype "bidirectional"))
      (node (ref "R8") (pin "1") (pinfunction "1_1") (pintype "passive"))
      (node (ref "U9") (pin "7") (pinfunction "TX+_7") (pintype "bidirectional"))
    )
    (net (code "164") (name "TD-_ESP32") (class "Default")
      (node (ref "D7") (pin "1") (pinfunction "IO1_1") (pintype "bidirectional"))
      (node (ref "J9") (pin "2") (pinfunction "TD-_2") (pintype "bidirectional"))
      (node (ref "R40") (pin "1") (pinfunction "1_1") (pintype "passive"))
      (node (ref "U7") (pin "6") (pinfunction "TX-_6") (pintype "bidirectional"))
    )
    (net (code "165") (name "TD-_MOSAIC") (class "Default")
      (node (ref "D1") (pin "4") (pinfunction "IO3_4") (pintype "bidirectional"))
      (node (ref "J2") (pin "2") (pinfunction "TD-_2") (pintype "bidirectional"))
      (node (ref "R9") (pin "1") (pinfunction "1_1") (pintype "passive"))
      (node (ref "U9") (pin "6") (pinfunction "TX-_6") (pintype "bidirectional"))
    )
    (net (code "166") (name "VCCA") (class "Default")
      (node (ref "C22") (pin "1") (pinfunction "1_1") (pintype "passive"))
      (node (ref "C38") (pin "1") (pinfunction "1_1") (pintype "passive"))
      (node (ref "C39") (pin "1") (pinfunction "1_1") (pintype "passive"))
      (node (ref "D7") (pin "5") (pinfunction "VCC_5") (pintype "bidirectional"))
      (node (ref "FB2") (pin "2") (pinfunction "2_2") (pintype "passive"))
      (node (ref "J9") (pin "4") (pinfunction "TCT_4") (pintype "bidirectional"))
      (node (ref "J9") (pin "5") (pinfunction "RCT_5") (pintype "bidirectional"))
      (node (ref "U7") (pin "3") (pinfunction "VDDA_3") (pintype "power_in"))
      (node (ref "VCCA") (pin "1") (pinfunction "1_1") (pintype "bidirectional"))
    )
    (net (code "167") (name "VCCIO") (class "Default")
      (node (ref "C43") (pin "1") (pinfunction "1_1") (pintype "passive"))
      (node (ref "C44") (pin "1") (pinfunction "1_1") (pintype "passive"))
      (node (ref "C45") (pin "1") (pinfunction "1_1") (pintype "passive"))
      (node (ref "C52") (pin "1") (pinfunction "1_1") (pintype "passive"))
      (node (ref "C55") (pin "1") (pinfunction "1_1") (pintype "passive"))
      (node (ref "C59") (pin "1") (pinfunction "1_1") (pintype "passive"))
      (node (ref "J13") (pin "2") (pinfunction "2_2") (pintype "passive"))
      (node (ref "J5") (pin "7") (pinfunction "7_7") (pintype "passive"))
      (node (ref "R23") (pin "1") (pinfunction "1_1") (pintype "passive"))
      (node (ref "U4") (pin "19") (pinfunction "VCCB_19") (pintype "bidirectional"))
      (node (ref "U5") (pin "19") (pinfunction "VCCB_19") (pintype "bidirectional"))
      (node (ref "VCCIO") (pin "2") (pinfunction "P_2") (pintype "passive"))
    )
    (net (code "168") (name "VDDA") (class "Default")
      (node (ref "C13") (pin "1") (pinfunction "1_1") (pintype "passive"))
      (node (ref "C24") (pin "1") (pinfunction "1_1") (pintype "passive"))
      (node (ref "C26") (pin "1") (pinfunction "1_1") (pintype "passive"))
      (node (ref "D1") (pin "5") (pinfunction "VCC_5") (pintype "bidirectional"))
      (node (ref "FB1") (pin "2") (pinfunction "2_2") (pintype "passive"))
      (node (ref "J2") (pin "4") (pinfunction "TCT_4") (pintype "bidirectional"))
      (node (ref "J2") (pin "5") (pinfunction "RCT_5") (pintype "bidirectional"))
      (node (ref "U9") (pin "3") (pinfunction "VDDA_3") (pintype "power_in"))
      (node (ref "VDDA") (pin "1") (pinfunction "1_1") (pintype "bidirectional"))
    )
    (net (code "169") (name "VIN") (class "Default")
      (node (ref "C85") (pin "1") (pinfunction "1_1") (pintype "passive"))
      (node (ref "D4") (pin "A") (pinfunction "A_A") (pintype "passive"))
      (node (ref "L4") (pin "2") (pinfunction "2_2") (pintype "passive"))
      (node (ref "VIN") (pin "1") (pinfunction "1_1") (pintype "bidirectional"))
    )
    (net (code "170") (name "VIN+") (class "Default")
      (node (ref "J5") (pin "10") (pinfunction "10_10") (pintype "passive"))
      (node (ref "VIN+") (pin "2") (pinfunction "2_2") (pintype "passive"))
      (node (ref "VIN+") (pin "4") (pinfunction "2_4") (pintype "passive"))
    )
    (net (code "171") (name "VIN-") (class "Default")
      (node (ref "J5") (pin "9") (pinfunction "9_9") (pintype "passive"))
      (node (ref "VIN-") (pin "1") (pinfunction "1_1") (pintype "passive"))
      (node (ref "VIN-") (pin "3") (pinfunction "1_3") (pintype "passive"))
    )
    (net (code "172") (name "V_POE") (class "Default")
      (node (ref "C47") (pin "1") (pinfunction "1_1") (pintype "passive"))
      (node (ref "D9") (pin "A") (pinfunction "A_A") (pintype "passive"))
      (node (ref "L1") (pin "2") (pinfunction "2_2") (pintype "passive"))
      (node (ref "LOAD") (pin "2") (pinfunction "2_2") (pintype "passive"))
      (node (ref "VPOE") (pin "1") (pinfunction "1_1") (pintype "bidirectional"))
    )
    (net (code "173") (name "V_USB") (class "Default")
      (node (ref "D10") (pin "5") (pinfunction "VCC_5") (pintype "bidirectional"))
      (node (ref "D5") (pin "A") (pinfunction "A_A") (pintype "passive"))
      (node (ref "J1") (pin "VBUS1") (pinfunction "VBUS_VBUS1") (pintype "bidirectional"))
      (node (ref "J1") (pin "VBUS2") (pinfunction "VBUS_VBUS2") (pintype "bidirectional"))
      (node (ref "VUSB") (pin "1") (pinfunction "1_1") (pintype "bidirectional"))
    )
    (net (code "174") (name "V_USB_2") (class "Default")
      (node (ref "D6") (pin "A") (pinfunction "A_A") (pintype "passive"))
      (node (ref "D8") (pin "5") (pinfunction "VCC_5") (pintype "bidirectional"))
      (node (ref "J6") (pin "VBUS1") (pinfunction "VBUS_VBUS1") (pintype "bidirectional"))
      (node (ref "J6") (pin "VBUS2") (pinfunction "VBUS_VBUS2") (pintype "bidirectional"))
      (node (ref "VUSB2") (pin "1") (pinfunction "1_1") (pintype "bidirectional"))
    )
    (net (code "175") (name "unconnected-(D8-IO3-Pad4)") (class "Default")
      (node (ref "D8") (pin "4") (pinfunction "IO3_4") (pintype "bidirectional"))
    )
    (net (code "176") (name "unconnected-(D8-IO4-Pad6)") (class "Default")
      (node (ref "D8") (pin "6") (pinfunction "IO4_6") (pintype "bidirectional"))
    )
    (net (code "177") (name "unconnected-(D10-IO3-Pad4)") (class "Default")
      (node (ref "D10") (pin "4") (pinfunction "IO3_4") (pintype "bidirectional"))
    )
    (net (code "178") (name "unconnected-(D10-IO4-Pad6)") (class "Default")
      (node (ref "D10") (pin "6") (pinfunction "IO4_6") (pintype "bidirectional"))
    )
    (net (code "179") (name "unconnected-(J3-DAT1-Pad8)") (class "Default")
      (node (ref "J3") (pin "8") (pinfunction "DAT1_8") (pintype "bidirectional"))
    )
    (net (code "180") (name "unconnected-(J3-DAT2-Pad1)") (class "Default")
      (node (ref "J3") (pin "1") (pinfunction "DAT2_1") (pintype "bidirectional"))
    )
    (net (code "181") (name "unconnected-(J3-DET-Pad9)") (class "Default")
      (node (ref "J3") (pin "9") (pinfunction "DET_9") (pintype "bidirectional"))
    )
    (net (code "182") (name "unconnected-(J9-PW+-Pad9)") (class "Default")
      (node (ref "J9") (pin "9") (pinfunction "PW+_9") (pintype "bidirectional"))
    )
    (net (code "183") (name "unconnected-(J9-PW--Pad10)") (class "Default")
      (node (ref "J9") (pin "10") (pinfunction "PW-_10") (pintype "bidirectional"))
    )
    (net (code "184") (name "unconnected-(U1-SENSOR_VN{slash}IA39-Pad5)") (class "Default")
      (node (ref "U1") (pin "5") (pinfunction "SENSOR_VN/IA39_5") (pintype "bidirectional"))
    )
    (net (code "185") (name "unconnected-(U1-SENSOR_VP{slash}IA36-Pad4)") (class "Default")
      (node (ref "U1") (pin "4") (pinfunction "SENSOR_VP/IA36_4") (pintype "bidirectional"))
    )
    (net (code "186") (name "unconnected-(U2-R232-Pad15)") (class "Default")
      (node (ref "U2") (pin "15") (pinfunction "R232_15") (pintype "bidirectional"))
    )
    (net (code "187") (name "unconnected-(U2-~{CTS}-Pad9)") (class "Default")
      (node (ref "U2") (pin "9") (pinfunction "~{CTS}_9") (pintype "bidirectional"))
    )
    (net (code "188") (name "unconnected-(U2-~{DCD}-Pad12)") (class "Default")
      (node (ref "U2") (pin "12") (pinfunction "~{DCD}_12") (pintype "bidirectional"))
    )
    (net (code "189") (name "unconnected-(U2-~{DSR}-Pad10)") (class "Default")
      (node (ref "U2") (pin "10") (pinfunction "~{DSR}_10") (pintype "bidirectional"))
    )
    (net (code "190") (name "unconnected-(U2-~{RI}-Pad11)") (class "Default")
      (node (ref "U2") (pin "11") (pinfunction "~{RI}_11") (pintype "bidirectional"))
    )
    (net (code "191") (name "unconnected-(U5-A7-Pad8)") (class "Default")
      (node (ref "U5") (pin "8") (pinfunction "A7_8") (pintype "bidirectional"))
    )
    (net (code "192") (name "unconnected-(U5-A8-Pad9)") (class "Default")
      (node (ref "U5") (pin "9") (pinfunction "A8_9") (pintype "bidirectional"))
    )
    (net (code "193") (name "unconnected-(U5-B7-Pad13)") (class "Default")
      (node (ref "U5") (pin "13") (pinfunction "B7_13") (pintype "bidirectional"))
    )
    (net (code "194") (name "unconnected-(U5-B8-Pad12)") (class "Default")
      (node (ref "U5") (pin "12") (pinfunction "B8_12") (pintype "bidirectional"))
    )
    (net (code "195") (name "unconnected-(U7-CRS{slash}CONFIG1-Pad29)") (class "Default")
      (node (ref "U7") (pin "29") (pinfunction "CRS/CONFIG1_29") (pintype "bidirectional"))
    )
    (net (code "196") (name "unconnected-(U7-INTRP-Pad21)") (class "Default")
      (node (ref "U7") (pin "21") (pinfunction "INTRP_21") (pintype "bidirectional"))
    )
    (net (code "197") (name "unconnected-(U7-RXC-Pad19)") (class "Default")
      (node (ref "U7") (pin "19") (pinfunction "RXC_19") (pintype "bidirectional"))
    )
    (net (code "198") (name "unconnected-(U7-RXD2{slash}PHYAD1-Pad14)") (class "Default")
      (node (ref "U7") (pin "14") (pinfunction "RXD2/PHYAD1_14") (pintype "bidirectional"))
    )
    (net (code "199") (name "unconnected-(U7-RXD3{slash}PHYAD0-Pad13)") (class "Default")
      (node (ref "U7") (pin "13") (pinfunction "RXD3/PHYAD0_13") (pintype "bidirectional"))
    )
    (net (code "200") (name "unconnected-(U7-RXER{slash}ISO-Pad20)") (class "Default")
      (node (ref "U7") (pin "20") (pinfunction "RXER/ISO_20") (pintype "bidirectional"))
    )
    (net (code "201") (name "unconnected-(U7-TXC-Pad22)") (class "Default")
      (node (ref "U7") (pin "22") (pinfunction "TXC_22") (pintype "bidirectional"))
    )
    (net (code "202") (name "unconnected-(U7-TXD2-Pad26)") (class "Default")
      (node (ref "U7") (pin "26") (pinfunction "TXD2_26") (pintype "bidirectional"))
    )
    (net (code "203") (name "unconnected-(U7-TXD3-Pad27)") (class "Default")
      (node (ref "U7") (pin "27") (pinfunction "TXD3_27") (pintype "bidirectional"))
    )
    (net (code "204") (name "unconnected-(U7-XO-Pad8)") (class "Default")
      (node (ref "U7") (pin "8") (pinfunction "XO_8") (pintype "bidirectional"))
    )
    (net (code "205") (name "unconnected-(U8-ONOFF-PadA10)") (class "Default")
      (node (ref "U8") (pin "A10") (pinfunction "ONOFF_A10") (pintype "input"))
    )
    (net (code "206") (name "unconnected-(U8-PMIC_ON_REQ-PadB16)") (class "Default")
      (node (ref "U8") (pin "B16") (pinfunction "PMIC_ON_REQ_B16") (pintype "output"))
    )
    (net (code "207") (name "unconnected-(U8-RSVD_NC-PadA9)") (class "Default")
      (node (ref "U8") (pin "A9") (pinfunction "RSVD_NC_A9") (pintype "no_connect"))
    )
    (net (code "208") (name "unconnected-(U8-RSVD_NC-PadA13)") (class "Default")
      (node (ref "U8") (pin "A13") (pinfunction "RSVD_NC_A13") (pintype "no_connect"))
    )
    (net (code "209") (name "unconnected-(U8-RSVD_NC-PadAA3)") (class "Default")
      (node (ref "U8") (pin "AA3") (pinfunction "RSVD_NC_AA3") (pintype "no_connect"))
    )
    (net (code "210") (name "unconnected-(U8-RSVD_NC-PadAA5)") (class "Default")
      (node (ref "U8") (pin "AA5") (pinfunction "RSVD_NC_AA5") (pintype "no_connect"))
    )
    (net (code "211") (name "unconnected-(U8-RSVD_NC-PadAA6)") (class "Default")
      (node (ref "U8") (pin "AA6") (pinfunction "RSVD_NC_AA6") (pintype "no_connect"))
    )
    (net (code "212") (name "unconnected-(U8-RSVD_NC-PadAA7)") (class "Default")
      (node (ref "U8") (pin "AA7") (pinfunction "RSVD_NC_AA7") (pintype "no_connect"))
    )
    (net (code "213") (name "unconnected-(U8-RSVD_NC-PadAA8)") (class "Default")
      (node (ref "U8") (pin "AA8") (pinfunction "RSVD_NC_AA8") (pintype "no_connect"))
    )
    (net (code "214") (name "unconnected-(U8-RSVD_NC-PadAA9)") (class "Default")
      (node (ref "U8") (pin "AA9") (pinfunction "RSVD_NC_AA9") (pintype "no_connect"))
    )
    (net (code "215") (name "unconnected-(U8-RSVD_NC-PadAA10)") (class "Default")
      (node (ref "U8") (pin "AA10") (pinfunction "RSVD_NC_AA10") (pintype "no_connect"))
    )
    (net (code "216") (name "unconnected-(U8-RSVD_NC-PadAA11)") (class "Default")
      (node (ref "U8") (pin "AA11") (pinfunction "RSVD_NC_AA11") (pintype "no_connect"))
    )
    (net (code "217") (name "unconnected-(U8-RSVD_NC-PadAA12)") (class "Default")
      (node (ref "U8") (pin "AA12") (pinfunction "RSVD_NC_AA12") (pintype "no_connect"))
    )
    (net (code "218") (name "unconnected-(U8-RSVD_NC-PadAB9)") (class "Default")
      (node (ref "U8") (pin "AB9") (pinfunction "RSVD_NC_AB9") (pintype "no_connect"))
    )
    (net (code "219") (name "unconnected-(U8-RSVD_NC-PadAB10)") (class "Default")
      (node (ref "U8") (pin "AB10") (pinfunction "RSVD_NC_AB10") (pintype "no_connect"))
    )
    (net (code "220") (name "unconnected-(U8-RSVD_NC-PadAB11)") (class "Default")
      (node (ref "U8") (pin "AB11") (pinfunction "RSVD_NC_AB11") (pintype "no_connect"))
    )
    (net (code "221") (name "unconnected-(U8-RSVD_NC-PadAB12)") (class "Default")
      (node (ref "U8") (pin "AB12") (pinfunction "RSVD_NC_AB12") (pintype "no_connect"))
    )
    (net (code "222") (name "unconnected-(U8-RSVD_NC-PadAC1)") (class "Default")
      (node (ref "U8") (pin "AC1") (pinfunction "RSVD_NC_AC1") (pintype "no_connect"))
    )
    (net (code "223") (name "unconnected-(U8-RSVD_NC-PadAC2)") (class "Default")
      (node (ref "U8") (pin "AC2") (pinfunction "RSVD_NC_AC2") (pintype "no_connect"))
    )
    (net (code "224") (name "unconnected-(U8-RSVD_NC-PadAC5)") (class "Default")
      (node (ref "U8") (pin "AC5") (pinfunction "RSVD_NC_AC5") (pintype "no_connect"))
    )
    (net (code "225") (name "unconnected-(U8-RSVD_NC-PadAC9)") (class "Default")
      (node (ref "U8") (pin "AC9") (pinfunction "RSVD_NC_AC9") (pintype "no_connect"))
    )
    (net (code "226") (name "unconnected-(U8-RSVD_NC-PadAC10)") (class "Default")
      (node (ref "U8") (pin "AC10") (pinfunction "RSVD_NC_AC10") (pintype "no_connect"))
    )
    (net (code "227") (name "unconnected-(U8-RSVD_NC-PadAC11)") (class "Default")
      (node (ref "U8") (pin "AC11") (pinfunction "RSVD_NC_AC11") (pintype "no_connect"))
    )
    (net (code "228") (name "unconnected-(U8-RSVD_NC-PadAC12)") (class "Default")
      (node (ref "U8") (pin "AC12") (pinfunction "RSVD_NC_AC12") (pintype "no_connect"))
    )
    (net (code "229") (name "unconnected-(U8-RSVD_NC-PadAC14)") (class "Default")
      (node (ref "U8") (pin "AC14") (pinfunction "RSVD_NC_AC14") (pintype "no_connect"))
    )
    (net (code "230") (name "unconnected-(U8-RSVD_NC-PadB3)") (class "Default")
      (node (ref "U8") (pin "B3") (pinfunction "RSVD_NC_B3") (pintype "no_connect"))
    )
    (net (code "231") (name "unconnected-(U8-RSVD_NC-PadB9)") (class "Default")
      (node (ref "U8") (pin "B9") (pinfunction "RSVD_NC_B9") (pintype "no_connect"))
    )
    (net (code "232") (name "unconnected-(U8-RSVD_NC-PadB10)") (class "Default")
      (node (ref "U8") (pin "B10") (pinfunction "RSVD_NC_B10") (pintype "no_connect"))
    )
    (net (code "233") (name "unconnected-(U8-RSVD_NC-PadB11)") (class "Default")
      (node (ref "U8") (pin "B11") (pinfunction "RSVD_NC_B11") (pintype "no_connect"))
    )
    (net (code "234") (name "unconnected-(U8-RSVD_NC-PadB12)") (class "Default")
      (node (ref "U8") (pin "B12") (pinfunction "RSVD_NC_B12") (pintype "no_connect"))
    )
    (net (code "235") (name "unconnected-(U8-RSVD_NC-PadB14)") (class "Default")
      (node (ref "U8") (pin "B14") (pinfunction "RSVD_NC_B14") (pintype "no_connect"))
    )
    (net (code "236") (name "unconnected-(U8-RSVD_NC-PadB15)") (class "Default")
      (node (ref "U8") (pin "B15") (pinfunction "RSVD_NC_B15") (pintype "no_connect"))
    )
    (net (code "237") (name "unconnected-(U8-RSVD_NC-PadB22)") (class "Default")
      (node (ref "U8") (pin "B22") (pinfunction "RSVD_NC_B22") (pintype "no_connect"))
    )
    (net (code "238") (name "unconnected-(U8-RSVD_NC-PadB23)") (class "Default")
      (node (ref "U8") (pin "B23") (pinfunction "RSVD_NC_B23") (pintype "no_connect"))
    )
    (net (code "239") (name "unconnected-(U8-RSVD_NC-PadC2)") (class "Default")
      (node (ref "U8") (pin "C2") (pinfunction "RSVD_NC_C2") (pintype "no_connect"))
    )
    (net (code "240") (name "unconnected-(U8-RSVD_NC-PadC3)") (class "Default")
      (node (ref "U8") (pin "C3") (pinfunction "RSVD_NC_C3") (pintype "no_connect"))
    )
    (net (code "241") (name "unconnected-(U8-RSVD_NC-PadC5)") (class "Default")
      (node (ref "U8") (pin "C5") (pinfunction "RSVD_NC_C5") (pintype "no_connect"))
    )
    (net (code "242") (name "unconnected-(U8-RSVD_NC-PadC6)") (class "Default")
      (node (ref "U8") (pin "C6") (pinfunction "RSVD_NC_C6") (pintype "no_connect"))
    )
    (net (code "243") (name "unconnected-(U8-RSVD_NC-PadC8)") (class "Default")
      (node (ref "U8") (pin "C8") (pinfunction "RSVD_NC_C8") (pintype "no_connect"))
    )
    (net (code "244") (name "unconnected-(U8-RSVD_NC-PadC9)") (class "Default")
      (node (ref "U8") (pin "C9") (pinfunction "RSVD_NC_C9") (pintype "no_connect"))
    )
    (net (code "245") (name "unconnected-(U8-RSVD_NC-PadC10)") (class "Default")
      (node (ref "U8") (pin "C10") (pinfunction "RSVD_NC_C10") (pintype "no_connect"))
    )
    (net (code "246") (name "unconnected-(U8-RSVD_NC-PadC11)") (class "Default")
      (node (ref "U8") (pin "C11") (pinfunction "RSVD_NC_C11") (pintype "no_connect"))
    )
    (net (code "247") (name "unconnected-(U8-RSVD_NC-PadC12)") (class "Default")
      (node (ref "U8") (pin "C12") (pinfunction "RSVD_NC_C12") (pintype "no_connect"))
    )
    (net (code "248") (name "unconnected-(U8-RSVD_NC-PadC13)") (class "Default")
      (node (ref "U8") (pin "C13") (pinfunction "RSVD_NC_C13") (pintype "no_connect"))
    )
    (net (code "249") (name "unconnected-(U8-RSVD_NC-PadC14)") (class "Default")
      (node (ref "U8") (pin "C14") (pinfunction "RSVD_NC_C14") (pintype "no_connect"))
    )
    (net (code "250") (name "unconnected-(U8-RSVD_NC-PadC21)") (class "Default")
      (node (ref "U8") (pin "C21") (pinfunction "RSVD_NC_C21") (pintype "no_connect"))
    )
    (net (code "251") (name "unconnected-(U8-RSVD_NC-PadC22)") (class "Default")
      (node (ref "U8") (pin "C22") (pinfunction "RSVD_NC_C22") (pintype "no_connect"))
    )
    (net (code "252") (name "unconnected-(U8-RSVD_NC-PadF3)") (class "Default")
      (node (ref "U8") (pin "F3") (pinfunction "RSVD_NC_F3") (pintype "no_connect"))
    )
    (net (code "253") (name "unconnected-(U8-RSVD_NC-PadG3)") (class "Default")
      (node (ref "U8") (pin "G3") (pinfunction "RSVD_NC_G3") (pintype "no_connect"))
    )
    (net (code "254") (name "unconnected-(U8-RSVD_NC-PadG22)") (class "Default")
      (node (ref "U8") (pin "G22") (pinfunction "RSVD_NC_G22") (pintype "no_connect"))
    )
    (net (code "255") (name "unconnected-(U8-RSVD_NC-PadH3)") (class "Default")
      (node (ref "U8") (pin "H3") (pinfunction "RSVD_NC_H3") (pintype "no_connect"))
    )
    (net (code "256") (name "unconnected-(U8-RSVD_NC-PadJ3)") (class "Default")
      (node (ref "U8") (pin "J3") (pinfunction "RSVD_NC_J3") (pintype "no_connect"))
    )
    (net (code "257") (name "unconnected-(U8-RSVD_NC-PadN3)") (class "Default")
      (node (ref "U8") (pin "N3") (pinfunction "RSVD_NC_N3") (pintype "no_connect"))
    )
    (net (code "258") (name "unconnected-(U8-RSVD_NC-PadR1)") (class "Default")
      (node (ref "U8") (pin "R1") (pinfunction "RSVD_NC_R1") (pintype "no_connect"))
    )
    (net (code "259") (name "unconnected-(U8-RSVD_NC-PadT1)") (class "Default")
      (node (ref "U8") (pin "T1") (pinfunction "RSVD_NC_T1") (pintype "no_connect"))
    )
    (net (code "260") (name "unconnected-(U8-RSVD_NC-PadT3)") (class "Default")
      (node (ref "U8") (pin "T3") (pinfunction "RSVD_NC_T3") (pintype "no_connect"))
    )
    (net (code "261") (name "unconnected-(U8-RSVD_NC-PadU1)") (class "Default")
      (node (ref "U8") (pin "U1") (pinfunction "RSVD_NC_U1") (pintype "no_connect"))
    )
    (net (code "262") (name "unconnected-(U8-RSVD_NC-PadU3)") (class "Default")
      (node (ref "U8") (pin "U3") (pinfunction "RSVD_NC_U3") (pintype "no_connect"))
    )
    (net (code "263") (name "unconnected-(U8-RSVD_NC-PadV1)") (class "Default")
      (node (ref "U8") (pin "V1") (pinfunction "RSVD_NC_V1") (pintype "no_connect"))
    )
    (net (code "264") (name "unconnected-(U8-RSVD_NC-PadV3)") (class "Default")
      (node (ref "U8") (pin "V3") (pinfunction "RSVD_NC_V3") (pintype "no_connect"))
    )
    (net (code "265") (name "unconnected-(U8-RSVD_NC-PadW1)") (class "Default")
      (node (ref "U8") (pin "W1") (pinfunction "RSVD_NC_W1") (pintype "no_connect"))
    )
    (net (code "266") (name "unconnected-(U8-RSVD_NC-PadW3)") (class "Default")
      (node (ref "U8") (pin "W3") (pinfunction "RSVD_NC_W3") (pintype "no_connect"))
    )
    (net (code "267") (name "unconnected-(U8-RSVD_NC-PadY3)") (class "Default")
      (node (ref "U8") (pin "Y3") (pinfunction "RSVD_NC_Y3") (pintype "no_connect"))
    )
    (net (code "268") (name "unconnected-(U8-RTC_XTALO-PadA2)") (class "Default")
      (node (ref "U8") (pin "A2") (pinfunction "RTC_XTALO_A2") (pintype "output"))
    )
    (net (code "269") (name "unconnected-(U9-CRS{slash}CONFIG1-Pad29)") (class "Default")
      (node (ref "U9") (pin "29") (pinfunction "CRS/CONFIG1_29") (pintype "bidirectional"))
    )
    (net (code "270") (name "unconnected-(U9-INTRP-Pad21)") (class "Default")
      (node (ref "U9") (pin "21") (pinfunction "INTRP_21") (pintype "bidirectional"))
    )
    (net (code "271") (name "unconnected-(U9-RXC-Pad19)") (class "Default")
      (node (ref "U9") (pin "19") (pinfunction "RXC_19") (pintype "bidirectional"))
    )
    (net (code "272") (name "unconnected-(U9-RXD2{slash}PHYAD1-Pad14)") (class "Default")
      (node (ref "U9") (pin "14") (pinfunction "RXD2/PHYAD1_14") (pintype "bidirectional"))
    )
    (net (code "273") (name "unconnected-(U9-RXD3{slash}PHYAD0-Pad13)") (class "Default")
      (node (ref "U9") (pin "13") (pinfunction "RXD3/PHYAD0_13") (pintype "bidirectional"))
    )
    (net (code "274") (name "unconnected-(U9-TXC-Pad22)") (class "Default")
      (node (ref "U9") (pin "22") (pinfunction "TXC_22") (pintype "bidirectional"))
    )
    (net (code "275") (name "unconnected-(U9-TXD2-Pad26)") (class "Default")
      (node (ref "U9") (pin "26") (pinfunction "TXD2_26") (pintype "bidirectional"))
    )
    (net (code "276") (name "unconnected-(U9-TXD3-Pad27)") (class "Default")
      (node (ref "U9") (pin "27") (pinfunction "TXD3_27") (pintype "bidirectional"))
    )
    (net (code "277") (name "unconnected-(U9-XO-Pad8)") (class "Default")
      (node (ref "U9") (pin "8") (pinfunction "XO_8") (pintype "bidirectional"))
    )
    (net (code "278") (name "unconnected-(U10-ADJ-Pad4)") (class "Default")
      (node (ref "U10") (pin "4") (pinfunction "ADJ_4") (pintype "bidirectional"))
    )
    (net (code "279") (name "unconnected-(U11-B4-Pad11)") (class "Default")
      (node (ref "U11") (pin "11") (pinfunction "B4_11") (pintype "bidirectional"))
    )
    (net (code "280") (name "unconnected-(U17-CTRL-Pad1)") (class "Default")
      (node (ref "U17") (pin "1") (pinfunction "CTRL_1") (pintype "input"))
    )
    (net (code "281") (name "unconnected-(U17-TRIM-Pad5)") (class "Default")
      (node (ref "U17") (pin "5") (pinfunction "TRIM_5") (pintype "input"))
    )
    (net (code "282") (name "~{BOOT}") (class "Default")
      (node (ref "BOOT_SW") (pin "1") (pinfunction "1_1") (pintype "passive"))
      (node (ref "Q1") (pin "6") (pinfunction "C_6") (pintype "passive"))
      (node (ref "R16") (pin "1") (pinfunction "1_1") (pintype "passive"))
      (node (ref "R19") (pin "2") (pinfunction "2_2") (pintype "passive"))
      (node (ref "TP_BOOT") (pin "1") (pinfunction "1_1") (pintype "bidirectional"))
    )
    (net (code "283") (name "~{RESET}") (class "Default")
      (node (ref "C31") (pin "1") (pinfunction "1_1") (pintype "passive"))
      (node (ref "MOSAIC_RST") (pin "2") (pinfunction "2_2") (pintype "passive"))
      (node (ref "MOSAIC_RST") (pin "4") (pinfunction "2_4") (pintype "passive"))
      (node (ref "Q1") (pin "3") (pinfunction "C_3") (pintype "passive"))
      (node (ref "R3") (pin "1") (pinfunction "1_1") (pintype "passive"))
      (node (ref "RESET_SW") (pin "1") (pinfunction "1_1") (pintype "passive"))
      (node (ref "U1") (pin "3") (pinfunction "EN_3") (pintype "bidirectional"))
    )
  )
)
